# Logic_-_Copy.net
KiCad netlist of a schematic drawn in EAGLE
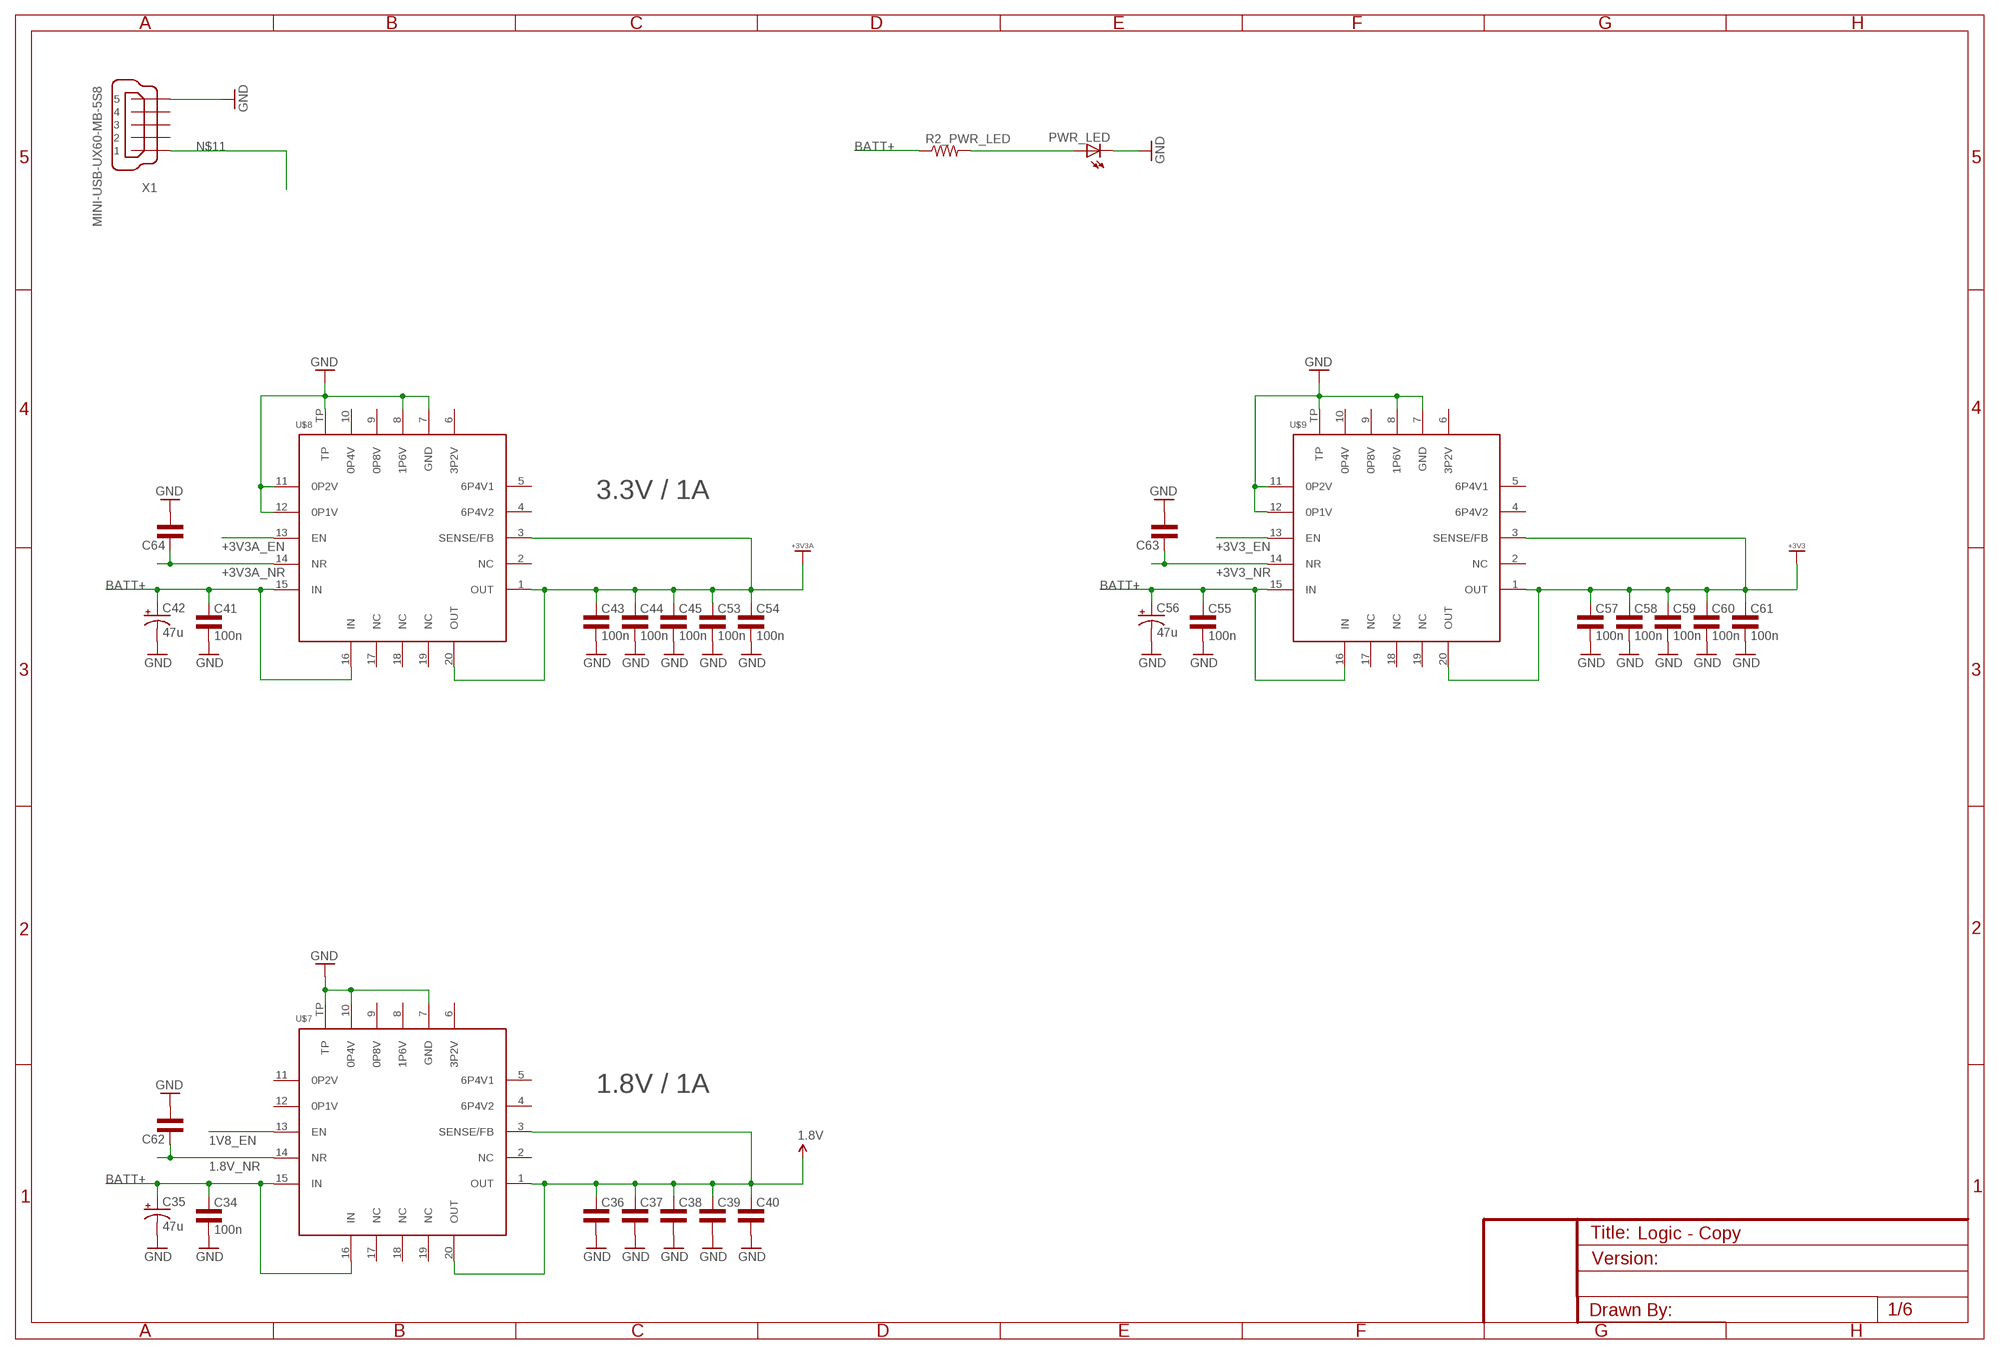
[diagram p0: schematic, sheet 1]
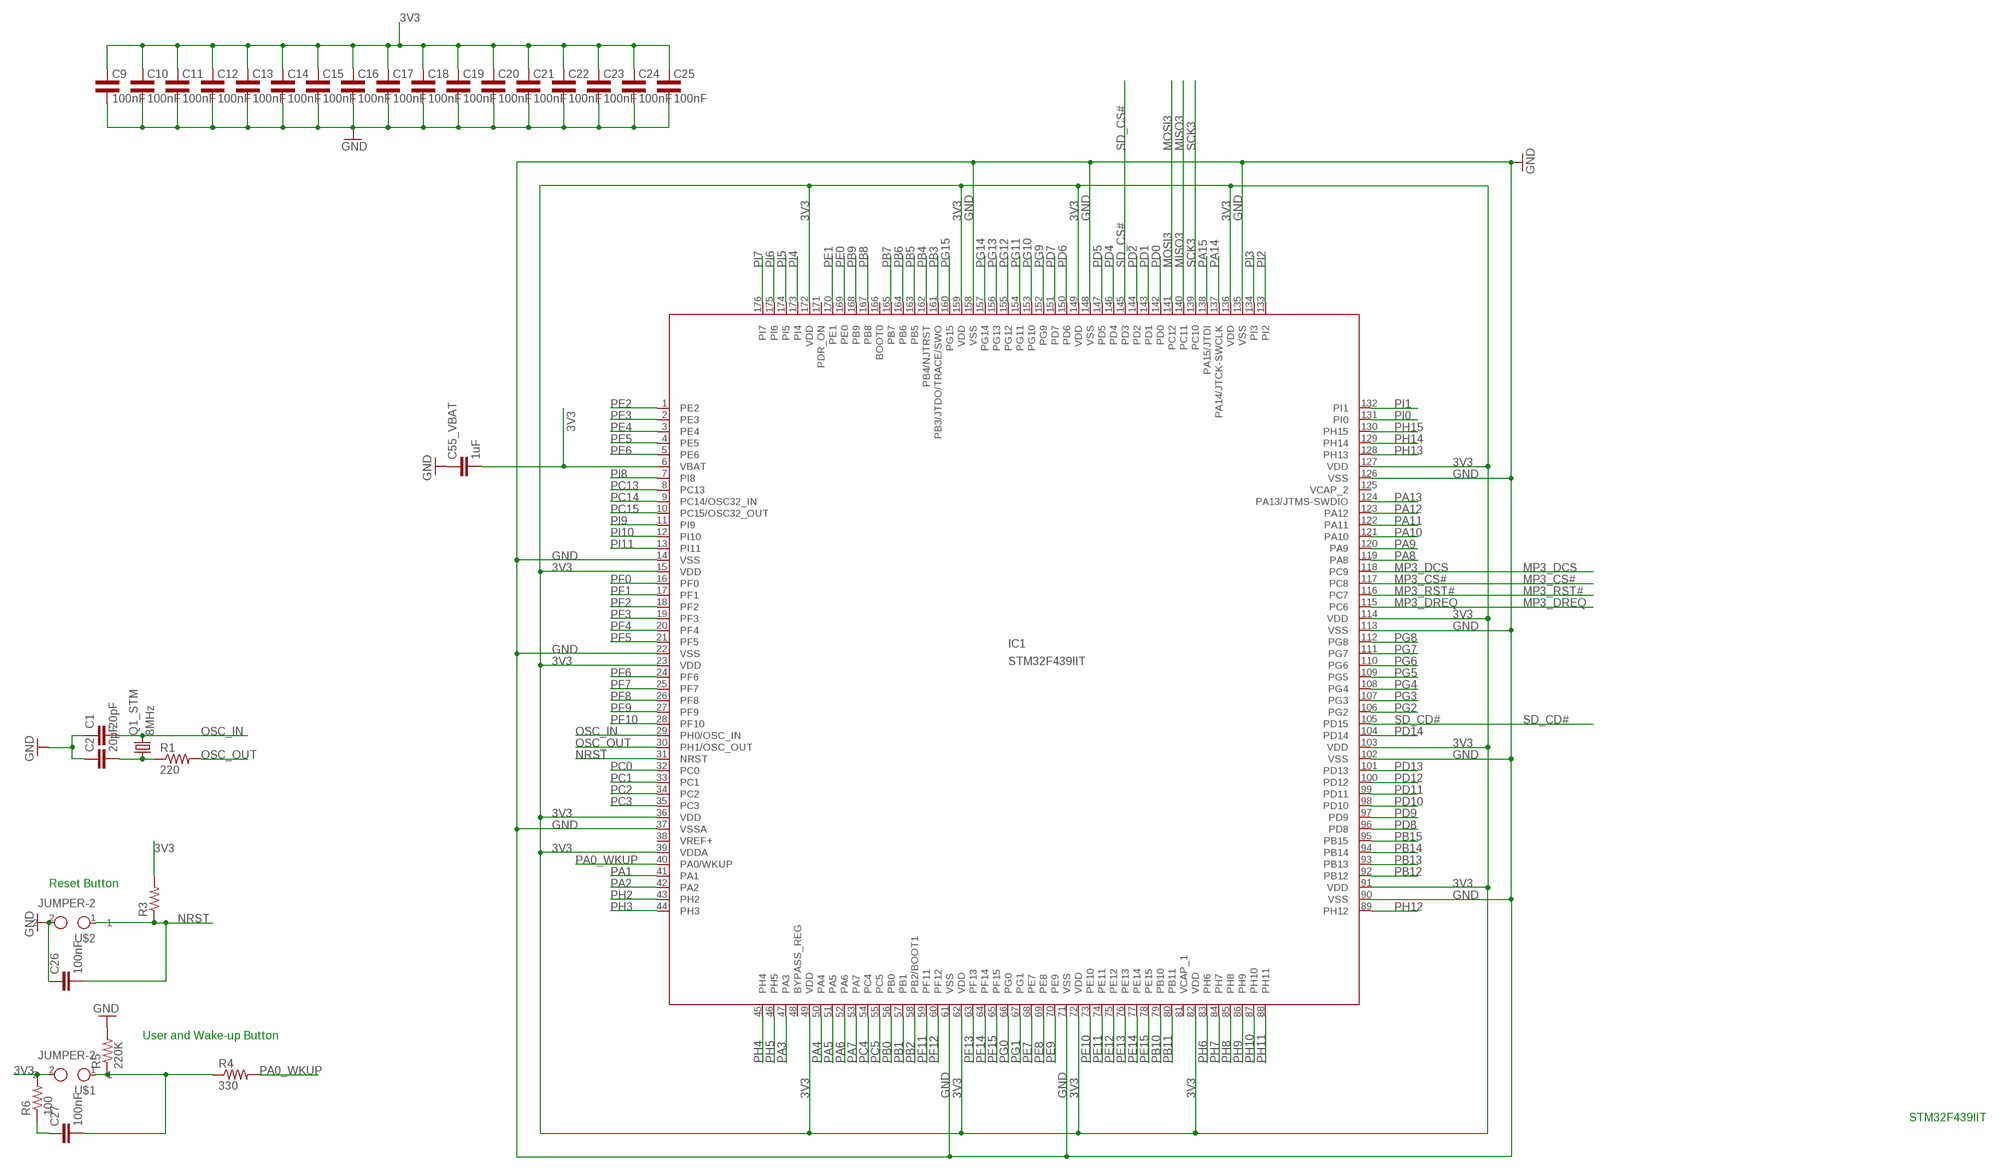
[diagram p1: schematic, sheet 2]
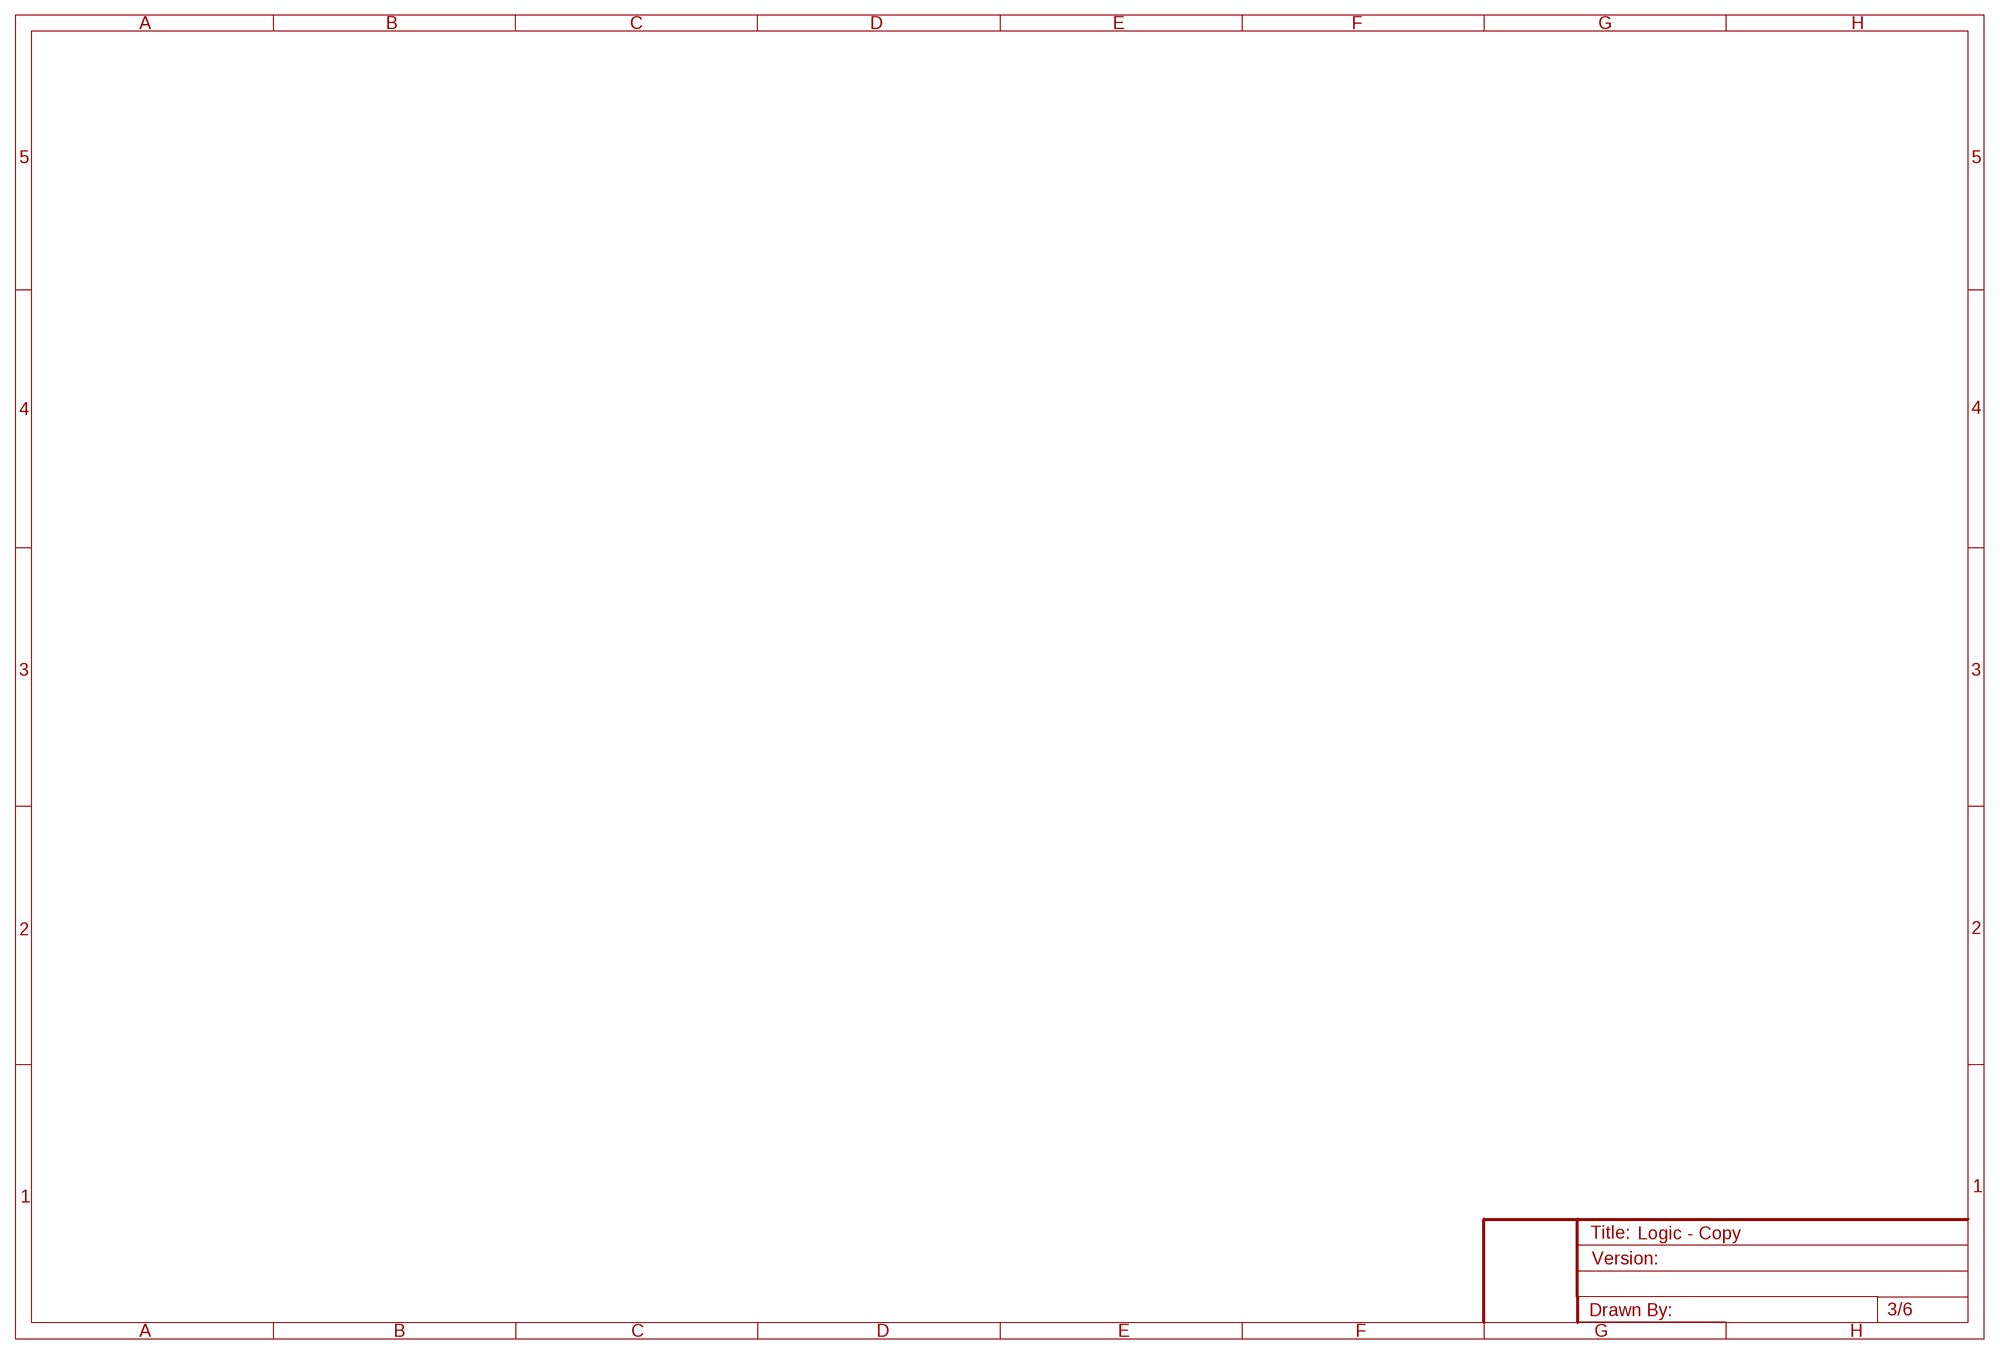
[diagram p2: schematic, sheet 3]
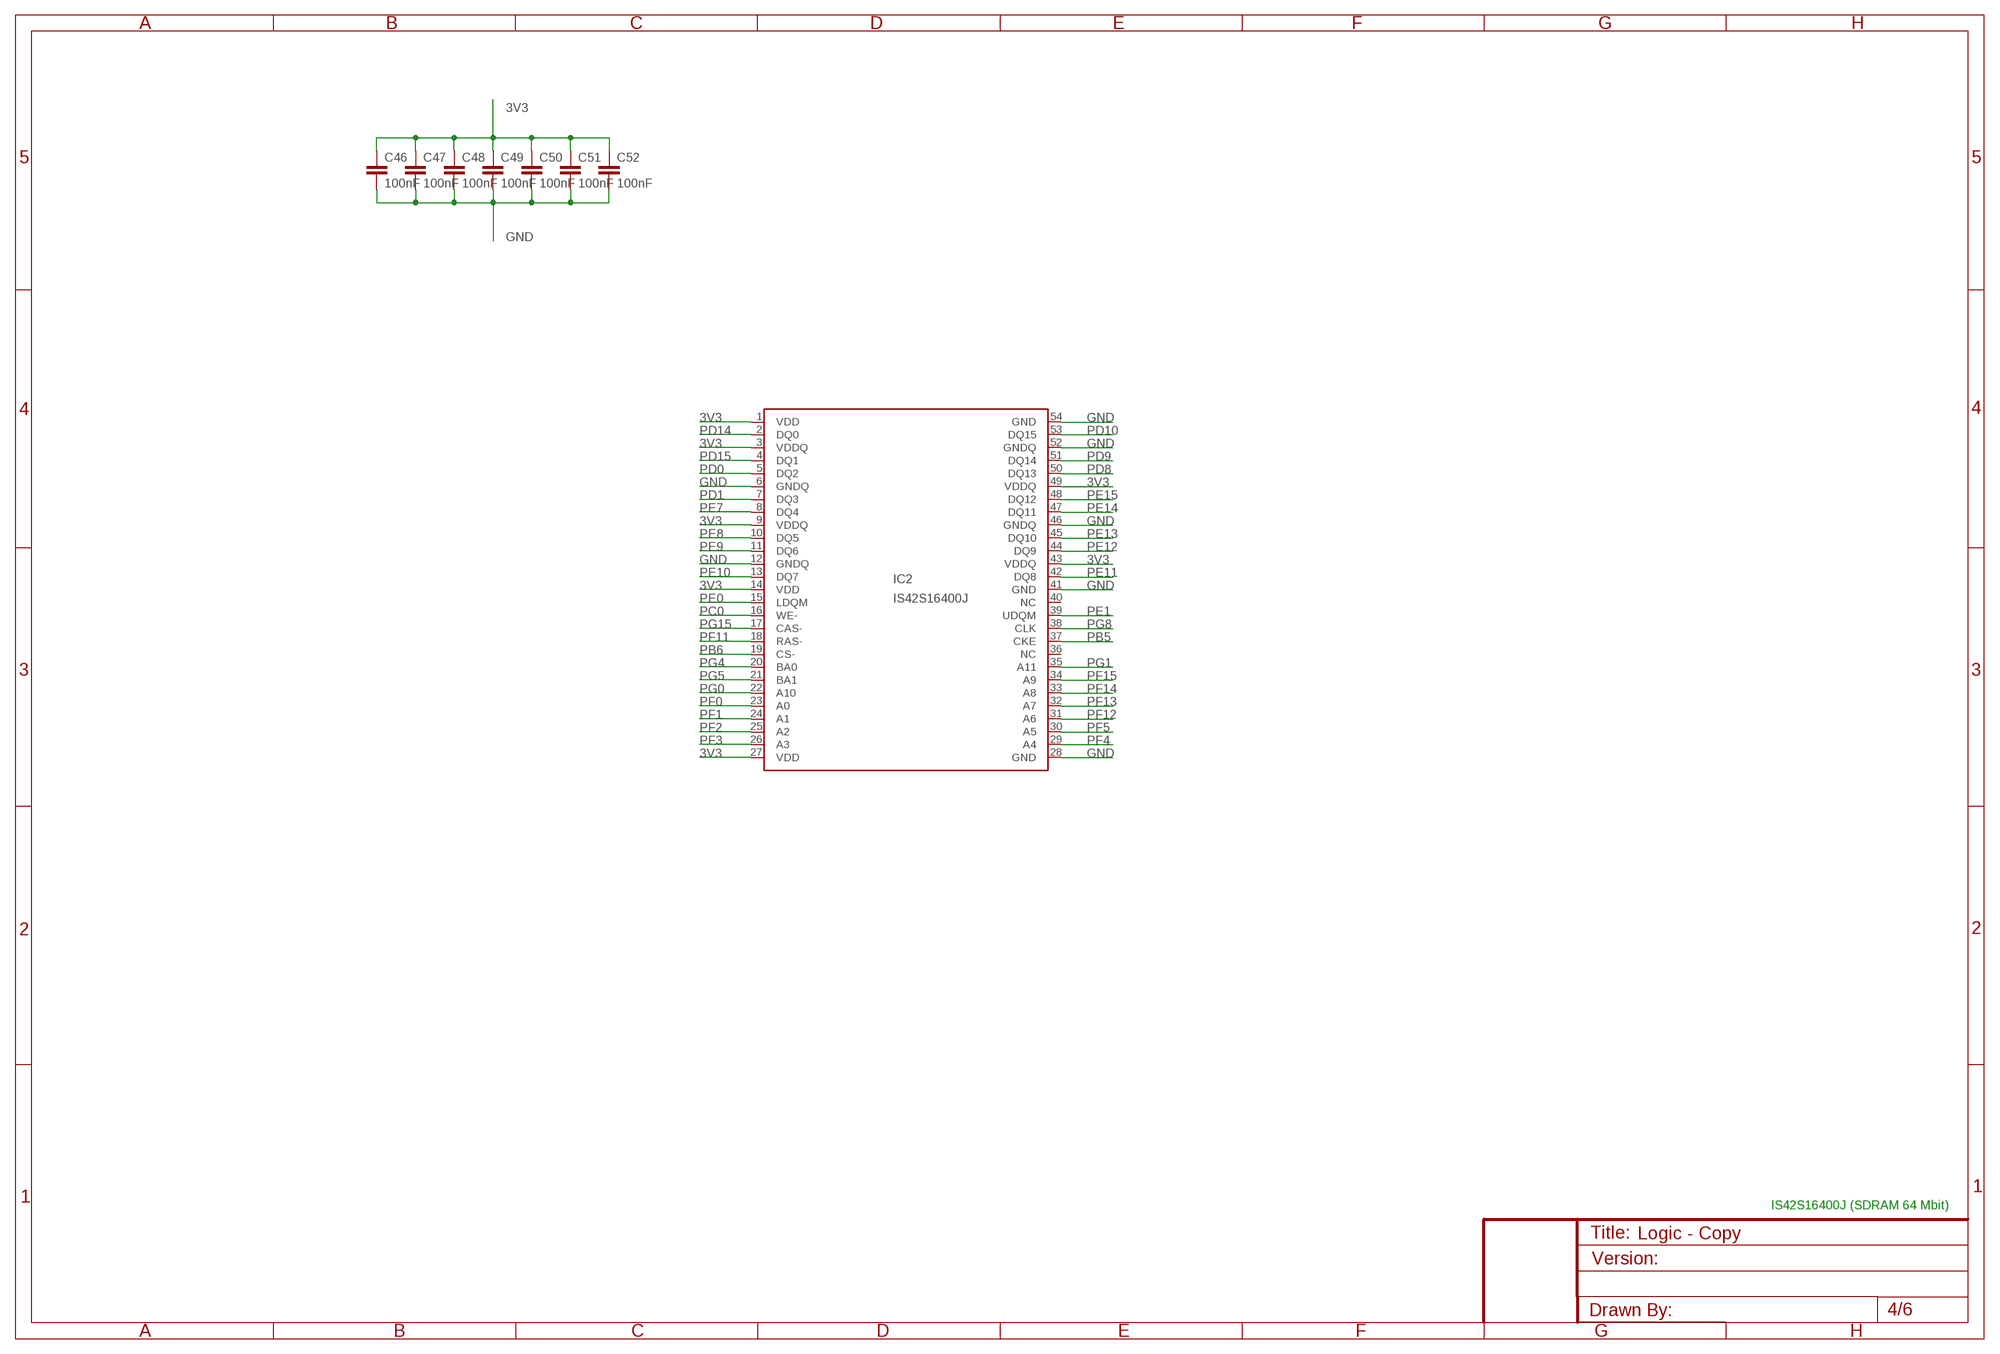
[diagram p3: schematic, sheet 4]
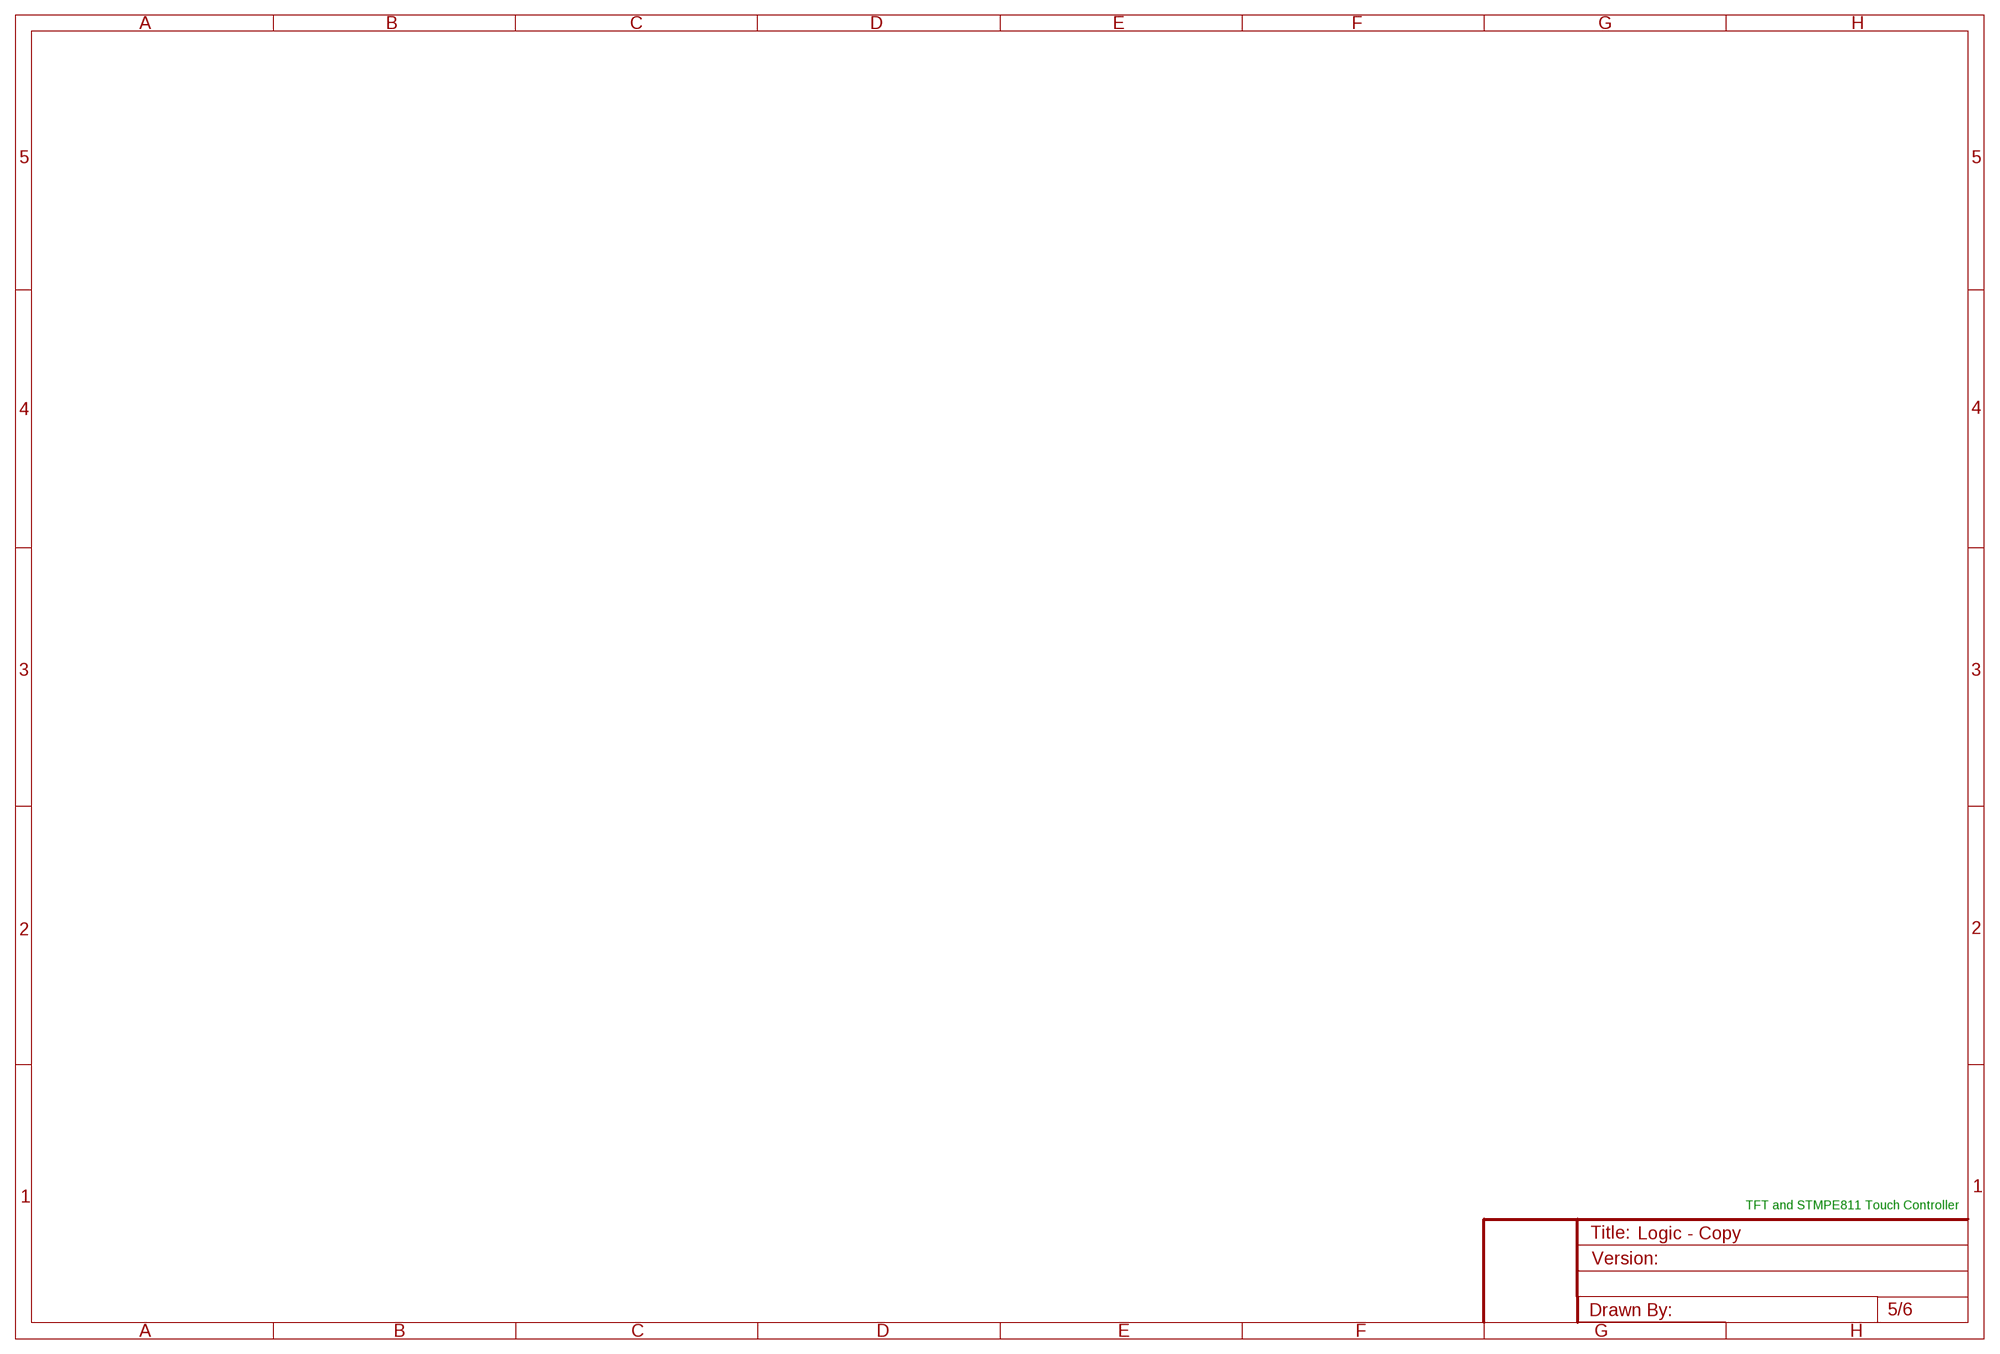
[diagram p4: schematic, sheet 5]
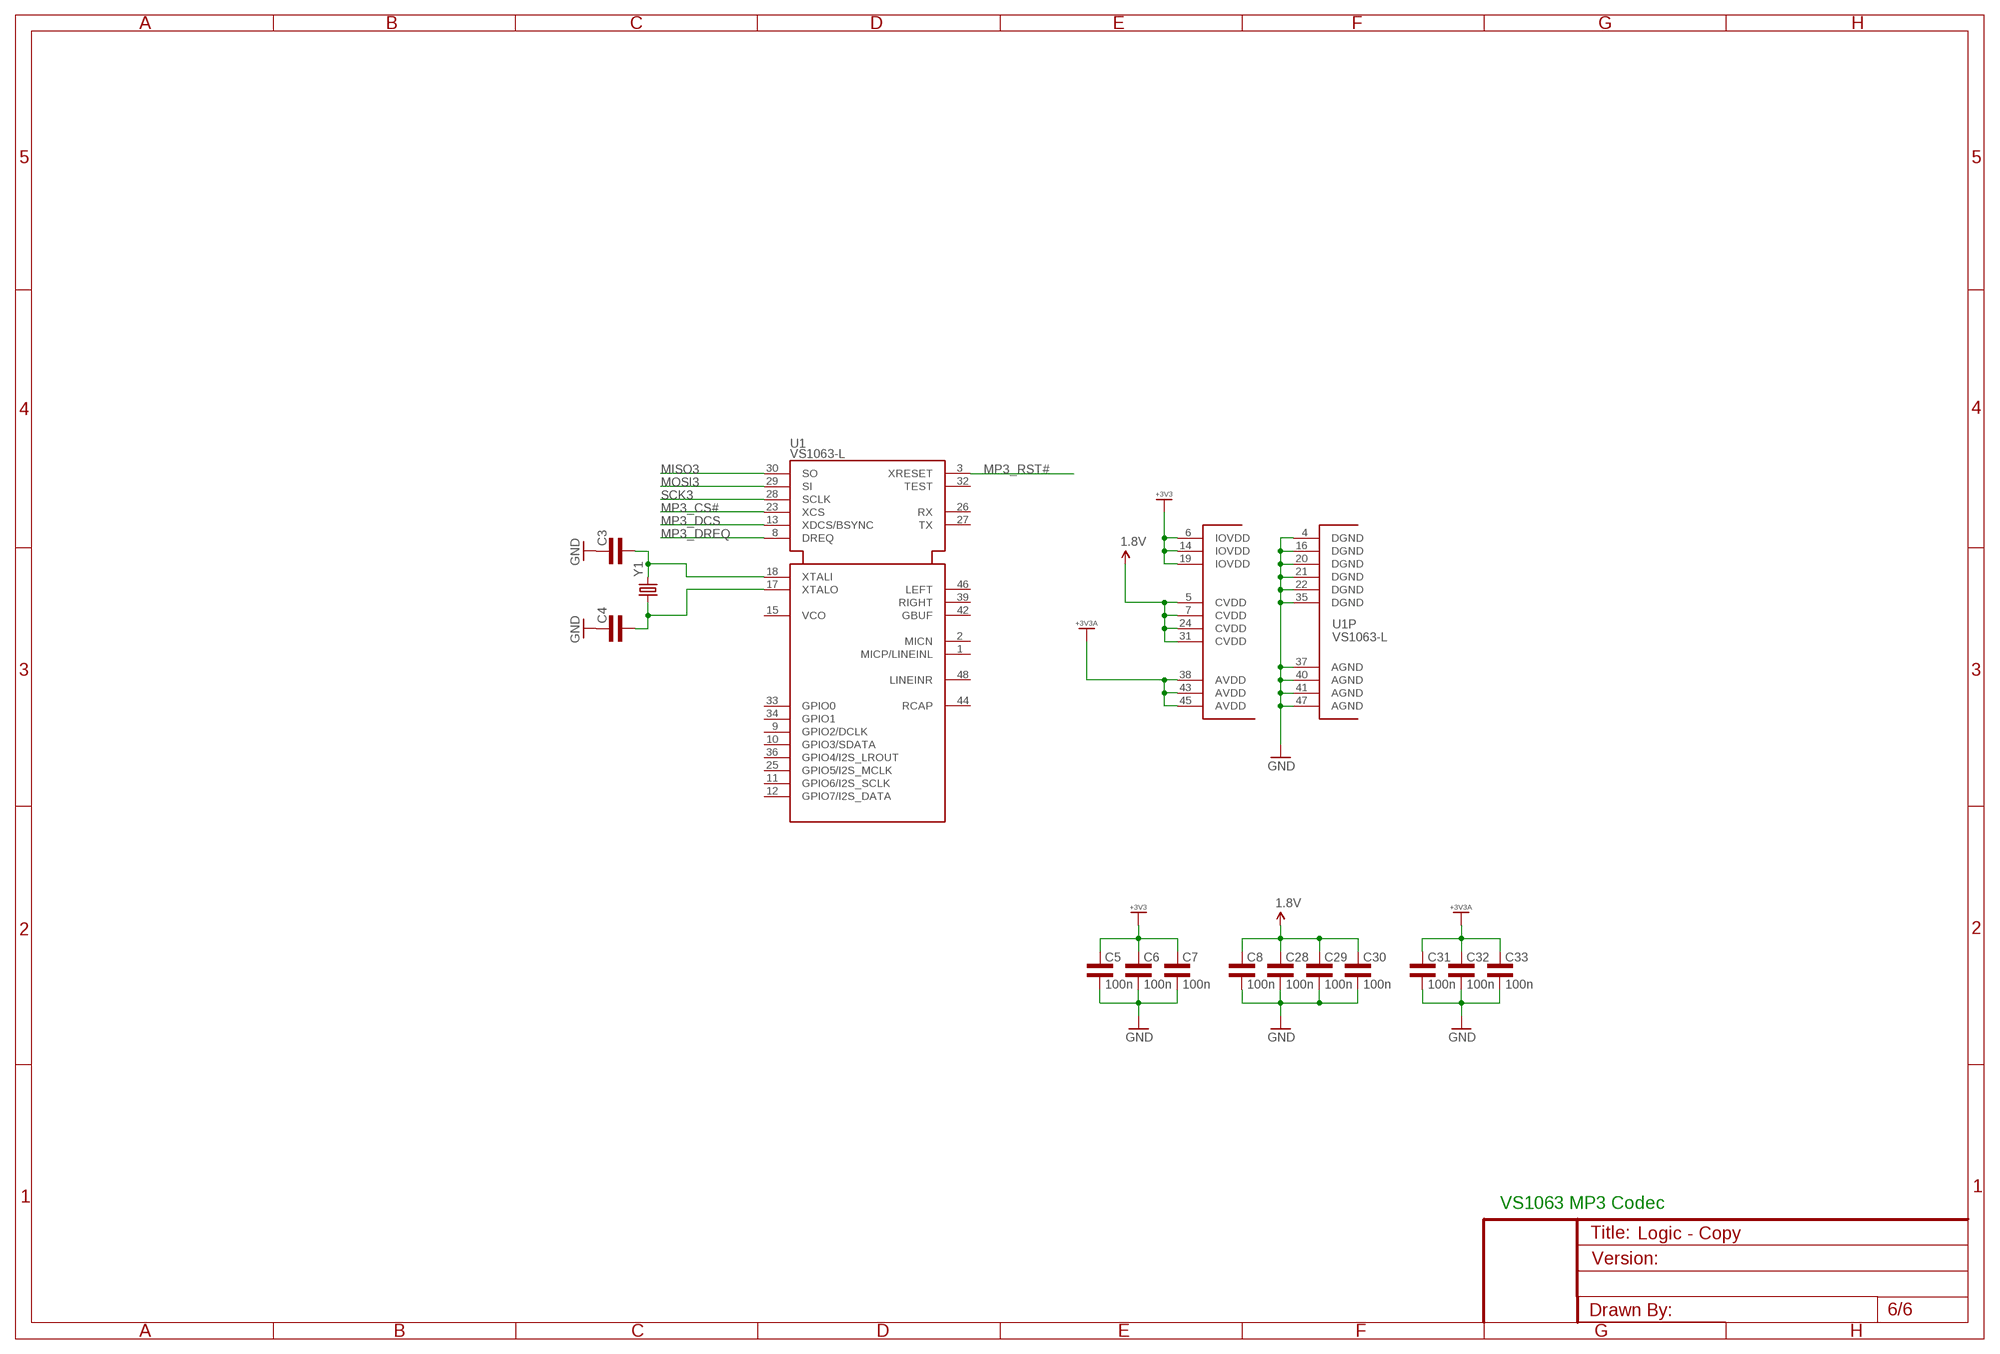
[diagram p5: schematic, sheet 6]

(export (version "E")
  (design (tool "Eeschema 10.0.6"))
  (components
    (comp (ref "C3")
      (value "CAP0603L3")
      (footprint "eagle-import:0603L3")
      (libsource (lib "eagle-import") (part "CAP0603L3"))
    )
    (comp (ref "C4")
      (value "CAP0603L3")
      (footprint "eagle-import:0603L3")
      (libsource (lib "eagle-import") (part "CAP0603L3"))
    )
    (comp (ref "C5")
      (value "100n")
      (footprint "eagle-import:0402L3")
      (libsource (lib "eagle-import") (part "CAP0402L3"))
    )
    (comp (ref "C6")
      (value "100n")
      (footprint "eagle-import:0402L3")
      (libsource (lib "eagle-import") (part "CAP0402L3"))
    )
    (comp (ref "C7")
      (value "100n")
      (footprint "eagle-import:0402L3")
      (libsource (lib "eagle-import") (part "CAP0402L3"))
    )
    (comp (ref "C8")
      (value "100n")
      (footprint "eagle-import:0402L3")
      (libsource (lib "eagle-import") (part "CAP0402L3"))
    )
    (comp (ref "C28")
      (value "100n")
      (footprint "eagle-import:0402L3")
      (libsource (lib "eagle-import") (part "CAP0402L3"))
    )
    (comp (ref "C29")
      (value "100n")
      (footprint "eagle-import:0402L3")
      (libsource (lib "eagle-import") (part "CAP0402L3"))
    )
    (comp (ref "C30")
      (value "100n")
      (footprint "eagle-import:0402L3")
      (libsource (lib "eagle-import") (part "CAP0402L3"))
    )
    (comp (ref "C31")
      (value "100n")
      (footprint "eagle-import:0402L3")
      (libsource (lib "eagle-import") (part "CAP0402L3"))
    )
    (comp (ref "C32")
      (value "100n")
      (footprint "eagle-import:0402L3")
      (libsource (lib "eagle-import") (part "CAP0402L3"))
    )
    (comp (ref "C33")
      (value "100n")
      (footprint "eagle-import:0402L3")
      (libsource (lib "eagle-import") (part "CAP0402L3"))
    )
    (comp (ref "U1")
      (value "VS1063-L")
      (footprint "eagle-import:LQFP48")
      (libsource (lib "eagle-import") (part "VS1063-L"))
    )
    (comp (ref "Y1")
      (value "CRYSTALHC49US")
      (footprint "eagle-import:HC49US")
      (libsource (lib "eagle-import") (part "CRYSTALHC49US"))
    )
    (comp (ref "C1")
      (value "20pF")
      (footprint "eagle-import:C0402")
      (libsource (lib "eagle-import") (part "resistor_C-EUC0402"))
    )
    (comp (ref "C2")
      (value "20pF")
      (footprint "eagle-import:C0402")
      (libsource (lib "eagle-import") (part "resistor_C-EUC0402"))
    )
    (comp (ref "C9")
      (value "100nF")
      (footprint "eagle-import:0402L3")
      (libsource (lib "eagle-import") (part "CAP0402L3"))
    )
    (comp (ref "C10")
      (value "100nF")
      (footprint "eagle-import:0402L3")
      (libsource (lib "eagle-import") (part "CAP0402L3"))
    )
    (comp (ref "C11")
      (value "100nF")
      (footprint "eagle-import:0402L3")
      (libsource (lib "eagle-import") (part "CAP0402L3"))
    )
    (comp (ref "C12")
      (value "100nF")
      (footprint "eagle-import:0402L3")
      (libsource (lib "eagle-import") (part "CAP0402L3"))
    )
    (comp (ref "C13")
      (value "100nF")
      (footprint "eagle-import:0402L3")
      (libsource (lib "eagle-import") (part "CAP0402L3"))
    )
    (comp (ref "C14")
      (value "100nF")
      (footprint "eagle-import:0402L3")
      (libsource (lib "eagle-import") (part "CAP0402L3"))
    )
    (comp (ref "C15")
      (value "100nF")
      (footprint "eagle-import:0402L3")
      (libsource (lib "eagle-import") (part "CAP0402L3"))
    )
    (comp (ref "C16")
      (value "100nF")
      (footprint "eagle-import:0402L3")
      (libsource (lib "eagle-import") (part "CAP0402L3"))
    )
    (comp (ref "C17")
      (value "100nF")
      (footprint "eagle-import:0402L3")
      (libsource (lib "eagle-import") (part "CAP0402L3"))
    )
    (comp (ref "C18")
      (value "100nF")
      (footprint "eagle-import:0402L3")
      (libsource (lib "eagle-import") (part "CAP0402L3"))
    )
    (comp (ref "C19")
      (value "100nF")
      (footprint "eagle-import:0402L3")
      (libsource (lib "eagle-import") (part "CAP0402L3"))
    )
    (comp (ref "C20")
      (value "100nF")
      (footprint "eagle-import:0402L3")
      (libsource (lib "eagle-import") (part "CAP0402L3"))
    )
    (comp (ref "C21")
      (value "100nF")
      (footprint "eagle-import:0402L3")
      (libsource (lib "eagle-import") (part "CAP0402L3"))
    )
    (comp (ref "C22")
      (value "100nF")
      (footprint "eagle-import:0402L3")
      (libsource (lib "eagle-import") (part "CAP0402L3"))
    )
    (comp (ref "C23")
      (value "100nF")
      (footprint "eagle-import:0402L3")
      (libsource (lib "eagle-import") (part "CAP0402L3"))
    )
    (comp (ref "C24")
      (value "100nF")
      (footprint "eagle-import:0402L3")
      (libsource (lib "eagle-import") (part "CAP0402L3"))
    )
    (comp (ref "C25")
      (value "100nF")
      (footprint "eagle-import:0402L3")
      (libsource (lib "eagle-import") (part "CAP0402L3"))
    )
    (comp (ref "C26")
      (value "100nF")
      (footprint "eagle-import:C0402")
      (libsource (lib "eagle-import") (part "C-EUC0402"))
    )
    (comp (ref "C27")
      (value "100nF")
      (footprint "eagle-import:C0402")
      (libsource (lib "eagle-import") (part "C-EUC0402"))
    )
    (comp (ref "C55_VBAT")
      (value "1uF")
      (footprint "eagle-import:C0402")
      (libsource (lib "eagle-import") (part "C-EUC0402"))
    )
    (comp (ref "IC1")
      (value "STM32F439IIT")
      (footprint "eagle-import:LQFP-176")
      (libsource (lib "eagle-import") (part "STM32F439IIT"))
    )
    (comp (ref "Q1_STM")
      (value "8MHz")
      (footprint "eagle-import:CTS406")
      (libsource (lib "eagle-import") (part "CRYSTALCTS406"))
    )
    (comp (ref "R1")
      (value "220")
      (footprint "eagle-import:0402-RES")
      (libsource (lib "eagle-import") (part "RESISTOR0402-RES"))
    )
    (comp (ref "R3")
      (value "RESISTOR0402-RES")
      (footprint "eagle-import:0402-RES")
      (libsource (lib "eagle-import") (part "RESISTOR0402-RES"))
    )
    (comp (ref "R4")
      (value "330")
      (footprint "eagle-import:0402-RES")
      (libsource (lib "eagle-import") (part "RESISTOR0402-RES"))
    )
    (comp (ref "R5")
      (value "220K")
      (footprint "eagle-import:0402-RES")
      (libsource (lib "eagle-import") (part "RESISTOR0402-RES"))
    )
    (comp (ref "R6")
      (value "100")
      (footprint "eagle-import:0402-RES")
      (libsource (lib "eagle-import") (part "RESISTOR0402-RES"))
    )
    (comp (ref "U$1")
      (value "JUMPER-2")
      (footprint "eagle-import:1X02")
      (libsource (lib "eagle-import") (part "JUMPER-2"))
    )
    (comp (ref "U$2")
      (value "JUMPER-2")
      (footprint "eagle-import:1X02")
      (libsource (lib "eagle-import") (part "JUMPER-2"))
    )
    (comp (ref "C34")
      (value "100n")
      (footprint "eagle-import:0805L3")
      (libsource (lib "eagle-import") (part "CAP0805L3"))
    )
    (comp (ref "C35")
      (value "47u")
      (footprint "eagle-import:CT3528")
      (libsource (lib "eagle-import") (part "CPOL-USCT3528"))
    )
    (comp (ref "C36")
      (value "CAP0805L3")
      (footprint "eagle-import:0805L3")
      (libsource (lib "eagle-import") (part "CAP0805L3"))
    )
    (comp (ref "C37")
      (value "CAP0805L3")
      (footprint "eagle-import:0805L3")
      (libsource (lib "eagle-import") (part "CAP0805L3"))
    )
    (comp (ref "C38")
      (value "CAP0805L3")
      (footprint "eagle-import:0805L3")
      (libsource (lib "eagle-import") (part "CAP0805L3"))
    )
    (comp (ref "C39")
      (value "CAP0805L3")
      (footprint "eagle-import:0805L3")
      (libsource (lib "eagle-import") (part "CAP0805L3"))
    )
    (comp (ref "C40")
      (value "CAP0805L3")
      (footprint "eagle-import:0805L3")
      (libsource (lib "eagle-import") (part "CAP0805L3"))
    )
    (comp (ref "C41")
      (value "100n")
      (footprint "eagle-import:0805L3")
      (libsource (lib "eagle-import") (part "CAP0805L3"))
    )
    (comp (ref "C42")
      (value "47u")
      (footprint "eagle-import:CT3528")
      (libsource (lib "eagle-import") (part "CPOL-USCT3528"))
    )
    (comp (ref "C43")
      (value "100n")
      (footprint "eagle-import:0805L3")
      (libsource (lib "eagle-import") (part "CAP0805L3"))
    )
    (comp (ref "C44")
      (value "100n")
      (footprint "eagle-import:0805L3")
      (libsource (lib "eagle-import") (part "CAP0805L3"))
    )
    (comp (ref "C45")
      (value "100n")
      (footprint "eagle-import:0805L3")
      (libsource (lib "eagle-import") (part "CAP0805L3"))
    )
    (comp (ref "C53")
      (value "100n")
      (footprint "eagle-import:0805L3")
      (libsource (lib "eagle-import") (part "CAP0805L3"))
    )
    (comp (ref "C54")
      (value "100n")
      (footprint "eagle-import:0805L3")
      (libsource (lib "eagle-import") (part "CAP0805L3"))
    )
    (comp (ref "C55")
      (value "100n")
      (footprint "eagle-import:0805L3")
      (libsource (lib "eagle-import") (part "CAP0805L3"))
    )
    (comp (ref "C56")
      (value "47u")
      (footprint "eagle-import:CT3528")
      (libsource (lib "eagle-import") (part "CPOL-USCT3528"))
    )
    (comp (ref "C57")
      (value "100n")
      (footprint "eagle-import:0805L3")
      (libsource (lib "eagle-import") (part "CAP0805L3"))
    )
    (comp (ref "C58")
      (value "100n")
      (footprint "eagle-import:0805L3")
      (libsource (lib "eagle-import") (part "CAP0805L3"))
    )
    (comp (ref "C59")
      (value "100n")
      (footprint "eagle-import:0805L3")
      (libsource (lib "eagle-import") (part "CAP0805L3"))
    )
    (comp (ref "C60")
      (value "100n")
      (footprint "eagle-import:0805L3")
      (libsource (lib "eagle-import") (part "CAP0805L3"))
    )
    (comp (ref "C61")
      (value "100n")
      (footprint "eagle-import:0805L3")
      (libsource (lib "eagle-import") (part "CAP0805L3"))
    )
    (comp (ref "C62")
      (value "CAP0402L3")
      (footprint "eagle-import:0402L3")
      (libsource (lib "eagle-import") (part "CAP0402L3"))
    )
    (comp (ref "C63")
      (value "CAP0402L3")
      (footprint "eagle-import:0402L3")
      (libsource (lib "eagle-import") (part "CAP0402L3"))
    )
    (comp (ref "C64")
      (value "CAP0402L3")
      (footprint "eagle-import:0402L3")
      (libsource (lib "eagle-import") (part "CAP0402L3"))
    )
    (comp (ref "PWR_LED")
      (value "LEDCHIP-LED0603")
      (footprint "eagle-import:CHIP-LED0603")
      (libsource (lib "eagle-import") (part "LEDCHIP-LED0603"))
    )
    (comp (ref "R2_PWR_LED")
      (value "RESISTOR0402-RES")
      (footprint "eagle-import:0402-RES")
      (libsource (lib "eagle-import") (part "RESISTOR0402-RES"))
    )
    (comp (ref "U$7")
      (value "POWER-SUPPLY_POS_V1_TI_LDO_TPS7A4700")
      (footprint "eagle-import:POWER-SUPPLY_POS_V1_TI_LDO_VQFN-20")
      (libsource (lib "eagle-import") (part "POWER-SUPPLY_POS_V1_TI_LDO_TPS7A4700"))
    )
    (comp (ref "U$8")
      (value "POWER-SUPPLY_POS_V1_TI_LDO_TPS7A4700")
      (footprint "eagle-import:POWER-SUPPLY_POS_V1_TI_LDO_VQFN-20")
      (libsource (lib "eagle-import") (part "POWER-SUPPLY_POS_V1_TI_LDO_TPS7A4700"))
    )
    (comp (ref "U$9")
      (value "POWER-SUPPLY_POS_V1_TI_LDO_TPS7A4700")
      (footprint "eagle-import:POWER-SUPPLY_POS_V1_TI_LDO_VQFN-20")
      (libsource (lib "eagle-import") (part "POWER-SUPPLY_POS_V1_TI_LDO_TPS7A4700"))
    )
    (comp (ref "X1")
      (value "MINI-USB-UX60-MB-5S8")
      (footprint "eagle-import:UX60-MB-5S8")
      (libsource (lib "eagle-import") (part "MINI-USB-UX60-MB-5S8"))
    )
    (comp (ref "C46")
      (value "100nF")
      (footprint "eagle-import:C0402")
      (libsource (lib "eagle-import") (part "C-EUC0402"))
    )
    (comp (ref "C47")
      (value "100nF")
      (footprint "eagle-import:C0402")
      (libsource (lib "eagle-import") (part "C-EUC0402"))
    )
    (comp (ref "C48")
      (value "100nF")
      (footprint "eagle-import:C0402")
      (libsource (lib "eagle-import") (part "C-EUC0402"))
    )
    (comp (ref "C49")
      (value "100nF")
      (footprint "eagle-import:C0402")
      (libsource (lib "eagle-import") (part "C-EUC0402"))
    )
    (comp (ref "C50")
      (value "100nF")
      (footprint "eagle-import:C0402")
      (libsource (lib "eagle-import") (part "C-EUC0402"))
    )
    (comp (ref "C51")
      (value "100nF")
      (footprint "eagle-import:C0402")
      (libsource (lib "eagle-import") (part "C-EUC0402"))
    )
    (comp (ref "C52")
      (value "100nF")
      (footprint "eagle-import:C0402")
      (libsource (lib "eagle-import") (part "C-EUC0402"))
    )
    (comp (ref "IC2")
      (value "IS42S16400J")
      (footprint "eagle-import:TSOP-2")
      (libsource (lib "eagle-import") (part "IS42S16400J"))
    )
  )
  (nets
    (net (code "1") (name "+3V3") (class "Default")
      (node (ref "C5") (pin "P$1") (pinfunction "1_P$1") (pintype "bidirectional"))
      (node (ref "C57") (pin "1") (pinfunction "1_1") (pintype "bidirectional"))
      (node (ref "C58") (pin "1") (pinfunction "1_1") (pintype "bidirectional"))
      (node (ref "C59") (pin "1") (pinfunction "1_1") (pintype "bidirectional"))
      (node (ref "C6") (pin "P$1") (pinfunction "1_P$1") (pintype "bidirectional"))
      (node (ref "C60") (pin "1") (pinfunction "1_1") (pintype "bidirectional"))
      (node (ref "C61") (pin "1") (pinfunction "1_1") (pintype "bidirectional"))
      (node (ref "C7") (pin "P$1") (pinfunction "1_P$1") (pintype "bidirectional"))
      (node (ref "U$9") (pin "1") (pinfunction "OUT_1") (pintype "bidirectional"))
      (node (ref "U$9") (pin "20") (pinfunction "OUT_20") (pintype "bidirectional"))
      (node (ref "U$9") (pin "3") (pinfunction "SENSE/FB_3") (pintype "bidirectional"))
      (node (ref "U1") (pin "14") (pinfunction "IOVDD_14") (pintype "power_in"))
      (node (ref "U1") (pin "19") (pinfunction "IOVDD_19") (pintype "power_in"))
      (node (ref "U1") (pin "6") (pinfunction "IOVDD_6") (pintype "power_in"))
    )
    (net (code "2") (name "+3V3A") (class "Default")
      (node (ref "C31") (pin "P$1") (pinfunction "1_P$1") (pintype "bidirectional"))
      (node (ref "C32") (pin "P$1") (pinfunction "1_P$1") (pintype "bidirectional"))
      (node (ref "C33") (pin "P$1") (pinfunction "1_P$1") (pintype "bidirectional"))
      (node (ref "C43") (pin "1") (pinfunction "1_1") (pintype "bidirectional"))
      (node (ref "C44") (pin "1") (pinfunction "1_1") (pintype "bidirectional"))
      (node (ref "C45") (pin "1") (pinfunction "1_1") (pintype "bidirectional"))
      (node (ref "C53") (pin "1") (pinfunction "1_1") (pintype "bidirectional"))
      (node (ref "C54") (pin "1") (pinfunction "1_1") (pintype "bidirectional"))
      (node (ref "U$8") (pin "1") (pinfunction "OUT_1") (pintype "bidirectional"))
      (node (ref "U$8") (pin "20") (pinfunction "OUT_20") (pintype "bidirectional"))
      (node (ref "U$8") (pin "3") (pinfunction "SENSE/FB_3") (pintype "bidirectional"))
      (node (ref "U1") (pin "38") (pinfunction "AVDD_38") (pintype "power_in"))
      (node (ref "U1") (pin "43") (pinfunction "AVDD_43") (pintype "power_in"))
      (node (ref "U1") (pin "45") (pinfunction "AVDD_45") (pintype "power_in"))
    )
    (net (code "3") (name "+3V3A_EN") (class "Default")
      (node (ref "U$8") (pin "13") (pinfunction "EN_13") (pintype "bidirectional"))
    )
    (net (code "4") (name "+3V3A_NR") (class "Default")
      (node (ref "C64") (pin "P$1") (pinfunction "1_P$1") (pintype "bidirectional"))
      (node (ref "U$8") (pin "14") (pinfunction "NR_14") (pintype "bidirectional"))
    )
    (net (code "5") (name "+3V3_EN") (class "Default")
      (node (ref "U$9") (pin "13") (pinfunction "EN_13") (pintype "bidirectional"))
    )
    (net (code "6") (name "+3V3_NR") (class "Default")
      (node (ref "C63") (pin "P$1") (pinfunction "1_P$1") (pintype "bidirectional"))
      (node (ref "U$9") (pin "14") (pinfunction "NR_14") (pintype "bidirectional"))
    )
    (net (code "7") (name "1.8V") (class "Default")
      (node (ref "C28") (pin "P$1") (pinfunction "1_P$1") (pintype "bidirectional"))
      (node (ref "C29") (pin "P$1") (pinfunction "1_P$1") (pintype "bidirectional"))
      (node (ref "C30") (pin "P$1") (pinfunction "1_P$1") (pintype "bidirectional"))
      (node (ref "C36") (pin "1") (pinfunction "1_1") (pintype "bidirectional"))
      (node (ref "C37") (pin "1") (pinfunction "1_1") (pintype "bidirectional"))
      (node (ref "C38") (pin "1") (pinfunction "1_1") (pintype "bidirectional"))
      (node (ref "C39") (pin "1") (pinfunction "1_1") (pintype "bidirectional"))
      (node (ref "C40") (pin "1") (pinfunction "1_1") (pintype "bidirectional"))
      (node (ref "C8") (pin "P$1") (pinfunction "1_P$1") (pintype "bidirectional"))
      (node (ref "U$7") (pin "1") (pinfunction "OUT_1") (pintype "bidirectional"))
      (node (ref "U$7") (pin "20") (pinfunction "OUT_20") (pintype "bidirectional"))
      (node (ref "U$7") (pin "3") (pinfunction "SENSE/FB_3") (pintype "bidirectional"))
      (node (ref "U1") (pin "24") (pinfunction "CVDD_24") (pintype "power_in"))
      (node (ref "U1") (pin "31") (pinfunction "CVDD_31") (pintype "power_in"))
      (node (ref "U1") (pin "5") (pinfunction "CVDD_5") (pintype "power_in"))
      (node (ref "U1") (pin "7") (pinfunction "CVDD_7") (pintype "power_in"))
    )
    (net (code "8") (name "1.8V_NR") (class "Default")
      (node (ref "C62") (pin "P$1") (pinfunction "1_P$1") (pintype "bidirectional"))
      (node (ref "U$7") (pin "14") (pinfunction "NR_14") (pintype "bidirectional"))
    )
    (net (code "9") (name "1V8_EN") (class "Default")
      (node (ref "U$7") (pin "13") (pinfunction "EN_13") (pintype "bidirectional"))
    )
    (net (code "10") (name "3V3") (class "Default")
      (node (ref "C10") (pin "P$1") (pinfunction "1_P$1") (pintype "bidirectional"))
      (node (ref "C11") (pin "P$1") (pinfunction "1_P$1") (pintype "bidirectional"))
      (node (ref "C12") (pin "P$1") (pinfunction "1_P$1") (pintype "bidirectional"))
      (node (ref "C13") (pin "P$1") (pinfunction "1_P$1") (pintype "bidirectional"))
      (node (ref "C14") (pin "P$1") (pinfunction "1_P$1") (pintype "bidirectional"))
      (node (ref "C15") (pin "P$1") (pinfunction "1_P$1") (pintype "bidirectional"))
      (node (ref "C16") (pin "P$1") (pinfunction "1_P$1") (pintype "bidirectional"))
      (node (ref "C17") (pin "P$1") (pinfunction "1_P$1") (pintype "bidirectional"))
      (node (ref "C18") (pin "P$1") (pinfunction "1_P$1") (pintype "bidirectional"))
      (node (ref "C19") (pin "P$1") (pinfunction "1_P$1") (pintype "bidirectional"))
      (node (ref "C20") (pin "P$1") (pinfunction "1_P$1") (pintype "bidirectional"))
      (node (ref "C21") (pin "P$1") (pinfunction "1_P$1") (pintype "bidirectional"))
      (node (ref "C22") (pin "P$1") (pinfunction "1_P$1") (pintype "bidirectional"))
      (node (ref "C23") (pin "P$1") (pinfunction "1_P$1") (pintype "bidirectional"))
      (node (ref "C24") (pin "P$1") (pinfunction "1_P$1") (pintype "bidirectional"))
      (node (ref "C25") (pin "P$1") (pinfunction "1_P$1") (pintype "bidirectional"))
      (node (ref "C46") (pin "1") (pinfunction "1_1") (pintype "passive"))
      (node (ref "C47") (pin "1") (pinfunction "1_1") (pintype "passive"))
      (node (ref "C48") (pin "1") (pinfunction "1_1") (pintype "passive"))
      (node (ref "C49") (pin "1") (pinfunction "1_1") (pintype "passive"))
      (node (ref "C50") (pin "1") (pinfunction "1_1") (pintype "passive"))
      (node (ref "C51") (pin "1") (pinfunction "1_1") (pintype "passive"))
      (node (ref "C52") (pin "1") (pinfunction "1_1") (pintype "passive"))
      (node (ref "C55_VBAT") (pin "2") (pinfunction "2_2") (pintype "passive"))
      (node (ref "C9") (pin "P$1") (pinfunction "1_P$1") (pintype "bidirectional"))
      (node (ref "IC1") (pin "103") (pinfunction "VDD_103") (pintype "power_in"))
      (node (ref "IC1") (pin "114") (pinfunction "VDD_114") (pintype "power_in"))
      (node (ref "IC1") (pin "127") (pinfunction "VDD_127") (pintype "power_in"))
      (node (ref "IC1") (pin "136") (pinfunction "VDD_136") (pintype "power_in"))
      (node (ref "IC1") (pin "149") (pinfunction "VDD_149") (pintype "power_in"))
      (node (ref "IC1") (pin "15") (pinfunction "VDD_15") (pintype "power_in"))
      (node (ref "IC1") (pin "159") (pinfunction "VDD_159") (pintype "power_in"))
      (node (ref "IC1") (pin "172") (pinfunction "VDD_172") (pintype "power_in"))
      (node (ref "IC1") (pin "23") (pinfunction "VDD_23") (pintype "power_in"))
      (node (ref "IC1") (pin "36") (pinfunction "VDD_36") (pintype "power_in"))
      (node (ref "IC1") (pin "39") (pinfunction "VDDA_39") (pintype "power_in"))
      (node (ref "IC1") (pin "49") (pinfunction "VDD_49") (pintype "power_in"))
      (node (ref "IC1") (pin "6") (pinfunction "VBAT_6") (pintype "power_in"))
      (node (ref "IC1") (pin "62") (pinfunction "VDD_62") (pintype "bidirectional"))
      (node (ref "IC1") (pin "72") (pinfunction "VDD_72") (pintype "power_in"))
      (node (ref "IC1") (pin "82") (pinfunction "VDD_82") (pintype "power_in"))
      (node (ref "IC1") (pin "91") (pinfunction "VDD_91") (pintype "power_in"))
      (node (ref "IC2") (pin "1") (pinfunction "VDD_1") (pintype "power_in"))
      (node (ref "IC2") (pin "14") (pinfunction "VDD_14") (pintype "power_in"))
      (node (ref "IC2") (pin "27") (pinfunction "VDD_27") (pintype "power_in"))
      (node (ref "IC2") (pin "3") (pinfunction "VDDQ_3") (pintype "power_in"))
      (node (ref "IC2") (pin "43") (pinfunction "VDDQ_43") (pintype "power_in"))
      (node (ref "IC2") (pin "49") (pinfunction "VDDQ_49") (pintype "power_in"))
      (node (ref "IC2") (pin "9") (pinfunction "VDDQ_9") (pintype "power_in"))
      (node (ref "R3") (pin "2") (pinfunction "2_2") (pintype "passive"))
      (node (ref "R6") (pin "2") (pinfunction "2_2") (pintype "passive"))
      (node (ref "U$1") (pin "2") (pinfunction "2_2") (pintype "bidirectional"))
    )
    (net (code "11") (name "BATT+") (class "Default")
      (node (ref "C34") (pin "1") (pinfunction "1_1") (pintype "bidirectional"))
      (node (ref "C35") (pin "+") (pinfunction "+_+") (pintype "passive"))
      (node (ref "C41") (pin "1") (pinfunction "1_1") (pintype "bidirectional"))
      (node (ref "C42") (pin "+") (pinfunction "+_+") (pintype "passive"))
      (node (ref "C55") (pin "1") (pinfunction "1_1") (pintype "bidirectional"))
      (node (ref "C56") (pin "+") (pinfunction "+_+") (pintype "passive"))
      (node (ref "R2_PWR_LED") (pin "1") (pinfunction "1_1") (pintype "passive"))
      (node (ref "U$7") (pin "15") (pinfunction "IN_15") (pintype "bidirectional"))
      (node (ref "U$7") (pin "16") (pinfunction "IN_16") (pintype "bidirectional"))
      (node (ref "U$8") (pin "15") (pinfunction "IN_15") (pintype "bidirectional"))
      (node (ref "U$8") (pin "16") (pinfunction "IN_16") (pintype "bidirectional"))
      (node (ref "U$9") (pin "15") (pinfunction "IN_15") (pintype "bidirectional"))
      (node (ref "U$9") (pin "16") (pinfunction "IN_16") (pintype "bidirectional"))
    )
    (net (code "12") (name "GND") (class "Default")
      (node (ref "C1") (pin "1") (pinfunction "1_1") (pintype "passive"))
      (node (ref "C10") (pin "P$2") (pinfunction "2_P$2") (pintype "bidirectional"))
      (node (ref "C11") (pin "P$2") (pinfunction "2_P$2") (pintype "bidirectional"))
      (node (ref "C12") (pin "P$2") (pinfunction "2_P$2") (pintype "bidirectional"))
      (node (ref "C13") (pin "P$2") (pinfunction "2_P$2") (pintype "bidirectional"))
      (node (ref "C14") (pin "P$2") (pinfunction "2_P$2") (pintype "bidirectional"))
      (node (ref "C15") (pin "P$2") (pinfunction "2_P$2") (pintype "bidirectional"))
      (node (ref "C16") (pin "P$2") (pinfunction "2_P$2") (pintype "bidirectional"))
      (node (ref "C17") (pin "P$2") (pinfunction "2_P$2") (pintype "bidirectional"))
      (node (ref "C18") (pin "P$2") (pinfunction "2_P$2") (pintype "bidirectional"))
      (node (ref "C19") (pin "P$2") (pinfunction "2_P$2") (pintype "bidirectional"))
      (node (ref "C2") (pin "1") (pinfunction "1_1") (pintype "passive"))
      (node (ref "C20") (pin "P$2") (pinfunction "2_P$2") (pintype "bidirectional"))
      (node (ref "C21") (pin "P$2") (pinfunction "2_P$2") (pintype "bidirectional"))
      (node (ref "C22") (pin "P$2") (pinfunction "2_P$2") (pintype "bidirectional"))
      (node (ref "C23") (pin "P$2") (pinfunction "2_P$2") (pintype "bidirectional"))
      (node (ref "C24") (pin "P$2") (pinfunction "2_P$2") (pintype "bidirectional"))
      (node (ref "C25") (pin "P$2") (pinfunction "2_P$2") (pintype "bidirectional"))
      (node (ref "C26") (pin "1") (pinfunction "1_1") (pintype "passive"))
      (node (ref "C28") (pin "P$2") (pinfunction "2_P$2") (pintype "bidirectional"))
      (node (ref "C29") (pin "P$2") (pinfunction "2_P$2") (pintype "bidirectional"))
      (node (ref "C3") (pin "P$1") (pinfunction "1_P$1") (pintype "bidirectional"))
      (node (ref "C30") (pin "P$2") (pinfunction "2_P$2") (pintype "bidirectional"))
      (node (ref "C31") (pin "P$2") (pinfunction "2_P$2") (pintype "bidirectional"))
      (node (ref "C32") (pin "P$2") (pinfunction "2_P$2") (pintype "bidirectional"))
      (node (ref "C33") (pin "P$2") (pinfunction "2_P$2") (pintype "bidirectional"))
      (node (ref "C34") (pin "2") (pinfunction "2_2") (pintype "bidirectional"))
      (node (ref "C35") (pin "-") (pinfunction "-_-") (pintype "passive"))
      (node (ref "C36") (pin "2") (pinfunction "2_2") (pintype "bidirectional"))
      (node (ref "C37") (pin "2") (pinfunction "2_2") (pintype "bidirectional"))
      (node (ref "C38") (pin "2") (pinfunction "2_2") (pintype "bidirectional"))
      (node (ref "C39") (pin "2") (pinfunction "2_2") (pintype "bidirectional"))
      (node (ref "C4") (pin "P$1") (pinfunction "1_P$1") (pintype "bidirectional"))
      (node (ref "C40") (pin "2") (pinfunction "2_2") (pintype "bidirectional"))
      (node (ref "C41") (pin "2") (pinfunction "2_2") (pintype "bidirectional"))
      (node (ref "C42") (pin "-") (pinfunction "-_-") (pintype "passive"))
      (node (ref "C43") (pin "2") (pinfunction "2_2") (pintype "bidirectional"))
      (node (ref "C44") (pin "2") (pinfunction "2_2") (pintype "bidirectional"))
      (node (ref "C45") (pin "2") (pinfunction "2_2") (pintype "bidirectional"))
      (node (ref "C46") (pin "2") (pinfunction "2_2") (pintype "passive"))
      (node (ref "C47") (pin "2") (pinfunction "2_2") (pintype "passive"))
      (node (ref "C48") (pin "2") (pinfunction "2_2") (pintype "passive"))
      (node (ref "C49") (pin "2") (pinfunction "2_2") (pintype "passive"))
      (node (ref "C5") (pin "P$2") (pinfunction "2_P$2") (pintype "bidirectional"))
      (node (ref "C50") (pin "2") (pinfunction "2_2") (pintype "passive"))
      (node (ref "C51") (pin "2") (pinfunction "2_2") (pintype "passive"))
      (node (ref "C52") (pin "2") (pinfunction "2_2") (pintype "passive"))
      (node (ref "C53") (pin "2") (pinfunction "2_2") (pintype "bidirectional"))
      (node (ref "C54") (pin "2") (pinfunction "2_2") (pintype "bidirectional"))
      (node (ref "C55") (pin "2") (pinfunction "2_2") (pintype "bidirectional"))
      (node (ref "C55_VBAT") (pin "1") (pinfunction "1_1") (pintype "passive"))
      (node (ref "C56") (pin "-") (pinfunction "-_-") (pintype "passive"))
      (node (ref "C57") (pin "2") (pinfunction "2_2") (pintype "bidirectional"))
      (node (ref "C58") (pin "2") (pinfunction "2_2") (pintype "bidirectional"))
      (node (ref "C59") (pin "2") (pinfunction "2_2") (pintype "bidirectional"))
      (node (ref "C6") (pin "P$2") (pinfunction "2_P$2") (pintype "bidirectional"))
      (node (ref "C60") (pin "2") (pinfunction "2_2") (pintype "bidirectional"))
      (node (ref "C61") (pin "2") (pinfunction "2_2") (pintype "bidirectional"))
      (node (ref "C62") (pin "P$2") (pinfunction "2_P$2") (pintype "bidirectional"))
      (node (ref "C63") (pin "P$2") (pinfunction "2_P$2") (pintype "bidirectional"))
      (node (ref "C64") (pin "P$2") (pinfunction "2_P$2") (pintype "bidirectional"))
      (node (ref "C7") (pin "P$2") (pinfunction "2_P$2") (pintype "bidirectional"))
      (node (ref "C8") (pin "P$2") (pinfunction "2_P$2") (pintype "bidirectional"))
      (node (ref "C9") (pin "P$2") (pinfunction "2_P$2") (pintype "bidirectional"))
      (node (ref "IC1") (pin "102") (pinfunction "VSS_102") (pintype "power_in"))
      (node (ref "IC1") (pin "113") (pinfunction "VSS_113") (pintype "power_in"))
      (node (ref "IC1") (pin "126") (pinfunction "VSS_126") (pintype "power_in"))
      (node (ref "IC1") (pin "135") (pinfunction "VSS_135") (pintype "power_in"))
      (node (ref "IC1") (pin "14") (pinfunction "VSS_14") (pintype "power_in"))
      (node (ref "IC1") (pin "148") (pinfunction "VSS_148") (pintype "power_in"))
      (node (ref "IC1") (pin "158") (pinfunction "VSS_158") (pintype "power_in"))
      (node (ref "IC1") (pin "22") (pinfunction "VSS_22") (pintype "power_in"))
      (node (ref "IC1") (pin "37") (pinfunction "VSSA_37") (pintype "power_in"))
      (node (ref "IC1") (pin "61") (pinfunction "VSS_61") (pintype "power_in"))
      (node (ref "IC1") (pin "71") (pinfunction "VSS_71") (pintype "power_in"))
      (node (ref "IC1") (pin "90") (pinfunction "VSS_90") (pintype "power_in"))
      (node (ref "IC2") (pin "12") (pinfunction "GNDQ_12") (pintype "power_in"))
      (node (ref "IC2") (pin "28") (pinfunction "GND_28") (pintype "power_in"))
      (node (ref "IC2") (pin "41") (pinfunction "GND_41") (pintype "power_in"))
      (node (ref "IC2") (pin "46") (pinfunction "GNDQ_46") (pintype "power_in"))
      (node (ref "IC2") (pin "52") (pinfunction "GNDQ_52") (pintype "power_in"))
      (node (ref "IC2") (pin "54") (pinfunction "GND_54") (pintype "power_in"))
      (node (ref "IC2") (pin "6") (pinfunction "GNDQ_6") (pintype "power_in"))
      (node (ref "PWR_LED") (pin "C") (pinfunction "C_C") (pintype "passive"))
      (node (ref "R5") (pin "2") (pinfunction "2_2") (pintype "passive"))
      (node (ref "U$2") (pin "2") (pinfunction "2_2") (pintype "bidirectional"))
      (node (ref "U$7") (pin "10") (pinfunction "0P4V_10") (pintype "bidirectional"))
      (node (ref "U$7") (pin "7") (pinfunction "GND_7") (pintype "bidirectional"))
      (node (ref "U$7") (pin "TP") (pinfunction "TP_TP") (pintype "bidirectional"))
      (node (ref "U$8") (pin "11") (pinfunction "0P2V_11") (pintype "bidirectional"))
      (node (ref "U$8") (pin "12") (pinfunction "0P1V_12") (pintype "bidirectional"))
      (node (ref "U$8") (pin "7") (pinfunction "GND_7") (pintype "bidirectional"))
      (node (ref "U$8") (pin "8") (pinfunction "1P6V_8") (pintype "bidirectional"))
      (node (ref "U$8") (pin "TP") (pinfunction "TP_TP") (pintype "bidirectional"))
      (node (ref "U$9") (pin "11") (pinfunction "0P2V_11") (pintype "bidirectional"))
      (node (ref "U$9") (pin "12") (pinfunction "0P1V_12") (pintype "bidirectional"))
      (node (ref "U$9") (pin "7") (pinfunction "GND_7") (pintype "bidirectional"))
      (node (ref "U$9") (pin "8") (pinfunction "1P6V_8") (pintype "bidirectional"))
      (node (ref "U$9") (pin "TP") (pinfunction "TP_TP") (pintype "bidirectional"))
      (node (ref "U1") (pin "16") (pinfunction "DGND_16") (pintype "power_in"))
      (node (ref "U1") (pin "20") (pinfunction "DGND_20") (pintype "power_in"))
      (node (ref "U1") (pin "21") (pinfunction "DGND_21") (pintype "power_in"))
      (node (ref "U1") (pin "22") (pinfunction "DGND_22") (pintype "power_in"))
      (node (ref "U1") (pin "35") (pinfunction "DGND_35") (pintype "power_in"))
      (node (ref "U1") (pin "37") (pinfunction "AGND_37") (pintype "power_in"))
      (node (ref "U1") (pin "4") (pinfunction "DGND_4") (pintype "power_in"))
      (node (ref "U1") (pin "40") (pinfunction "AGND_40") (pintype "power_in"))
      (node (ref "U1") (pin "41") (pinfunction "AGND_41") (pintype "power_in"))
      (node (ref "U1") (pin "47") (pinfunction "AGND_47") (pintype "power_in"))
      (node (ref "X1") (pin "5") (pinfunction "5_5") (pintype "input"))
    )
    (net (code "13") (name "MISO3") (class "Default")
      (node (ref "IC1") (pin "140") (pinfunction "PC11_140") (pintype "bidirectional"))
      (node (ref "U1") (pin "30") (pinfunction "SO_30") (pintype "output"))
    )
    (net (code "14") (name "MOSI3") (class "Default")
      (node (ref "IC1") (pin "141") (pinfunction "PC12_141") (pintype "bidirectional"))
      (node (ref "U1") (pin "29") (pinfunction "SI_29") (pintype "input"))
    )
    (net (code "15") (name "MP3_CS#") (class "Default")
      (node (ref "IC1") (pin "117") (pinfunction "PC8_117") (pintype "bidirectional"))
      (node (ref "U1") (pin "23") (pinfunction "XCS_23") (pintype "input"))
    )
    (net (code "16") (name "MP3_DCS") (class "Default")
      (node (ref "IC1") (pin "118") (pinfunction "PC9_118") (pintype "bidirectional"))
      (node (ref "U1") (pin "13") (pinfunction "XDCS/BSYNC_13") (pintype "input"))
    )
    (net (code "17") (name "MP3_DREQ") (class "Default")
      (node (ref "IC1") (pin "115") (pinfunction "PC6_115") (pintype "bidirectional"))
      (node (ref "U1") (pin "8") (pinfunction "DREQ_8") (pintype "output"))
    )
    (net (code "18") (name "MP3_RST#") (class "Default")
      (node (ref "IC1") (pin "116") (pinfunction "PC7_116") (pintype "bidirectional"))
      (node (ref "U1") (pin "3") (pinfunction "XRESET_3") (pintype "input"))
    )
    (net (code "19") (name "N$11") (class "Default")
      (node (ref "X1") (pin "1") (pinfunction "1_1") (pintype "input"))
    )
    (net (code "20") (name "NRST") (class "Default")
      (node (ref "C26") (pin "2") (pinfunction "2_2") (pintype "passive"))
      (node (ref "IC1") (pin "31") (pinfunction "NRST_31") (pintype "bidirectional"))
      (node (ref "R3") (pin "1") (pinfunction "1_1") (pintype "passive"))
      (node (ref "U$2") (pin "1") (pinfunction "1_1") (pintype "bidirectional"))
    )
    (net (code "21") (name "Net-(C2-Pad2)") (class "Default")
      (node (ref "C2") (pin "2") (pinfunction "2_2") (pintype "passive"))
      (node (ref "Q1_STM") (pin "1") (pinfunction "1_1") (pintype "passive"))
      (node (ref "R1") (pin "1") (pinfunction "1_1") (pintype "passive"))
    )
    (net (code "22") (name "Net-(C3-2)") (class "Default")
      (node (ref "C3") (pin "P$2") (pinfunction "2_P$2") (pintype "bidirectional"))
      (node (ref "U1") (pin "18") (pinfunction "XTALI_18") (pintype "input"))
      (node (ref "Y1") (pin "2") (pinfunction "2_2") (pintype "passive"))
    )
    (net (code "23") (name "Net-(C4-2)") (class "Default")
      (node (ref "C4") (pin "P$2") (pinfunction "2_P$2") (pintype "bidirectional"))
      (node (ref "U1") (pin "17") (pinfunction "XTALO_17") (pintype "output"))
      (node (ref "Y1") (pin "1") (pinfunction "1_1") (pintype "passive"))
    )
    (net (code "24") (name "Net-(C27-Pad1)") (class "Default")
      (node (ref "C27") (pin "1") (pinfunction "1_1") (pintype "passive"))
      (node (ref "R6") (pin "1") (pinfunction "1_1") (pintype "passive"))
    )
    (net (code "25") (name "Net-(C27-Pad2)") (class "Default")
      (node (ref "C27") (pin "2") (pinfunction "2_2") (pintype "passive"))
      (node (ref "R4") (pin "1") (pinfunction "1_1") (pintype "passive"))
      (node (ref "R5") (pin "1") (pinfunction "1_1") (pintype "passive"))
      (node (ref "U$1") (pin "1") (pinfunction "1_1") (pintype "bidirectional"))
    )
    (net (code "26") (name "Net-(PWR_LED-PadA)") (class "Default")
      (node (ref "PWR_LED") (pin "A") (pinfunction "A_A") (pintype "passive"))
      (node (ref "R2_PWR_LED") (pin "2") (pinfunction "2_2") (pintype "passive"))
    )
    (net (code "27") (name "OSC_IN") (class "Default")
      (node (ref "C1") (pin "2") (pinfunction "2_2") (pintype "passive"))
      (node (ref "IC1") (pin "29") (pinfunction "PH0/OSC_IN_29") (pintype "bidirectional"))
      (node (ref "Q1_STM") (pin "3") (pinfunction "2_3") (pintype "passive"))
    )
    (net (code "28") (name "OSC_OUT") (class "Default")
      (node (ref "IC1") (pin "30") (pinfunction "PH1/OSC_OUT_30") (pintype "bidirectional"))
      (node (ref "R1") (pin "2") (pinfunction "2_2") (pintype "passive"))
    )
    (net (code "29") (name "PA0_WKUP") (class "Default")
      (node (ref "IC1") (pin "40") (pinfunction "PA0/WKUP_40") (pintype "bidirectional"))
      (node (ref "R4") (pin "2") (pinfunction "2_2") (pintype "passive"))
    )
    (net (code "30") (name "PA1") (class "Default")
      (node (ref "IC1") (pin "41") (pinfunction "PA1_41") (pintype "bidirectional"))
    )
    (net (code "31") (name "PA2") (class "Default")
      (node (ref "IC1") (pin "42") (pinfunction "PA2_42") (pintype "bidirectional"))
    )
    (net (code "32") (name "PA3") (class "Default")
      (node (ref "IC1") (pin "47") (pinfunction "PA3_47") (pintype "bidirectional"))
    )
    (net (code "33") (name "PA4") (class "Default")
      (node (ref "IC1") (pin "50") (pinfunction "PA4_50") (pintype "bidirectional"))
    )
    (net (code "34") (name "PA5") (class "Default")
      (node (ref "IC1") (pin "51") (pinfunction "PA5_51") (pintype "bidirectional"))
    )
    (net (code "35") (name "PA6") (class "Default")
      (node (ref "IC1") (pin "52") (pinfunction "PA6_52") (pintype "bidirectional"))
    )
    (net (code "36") (name "PA7") (class "Default")
      (node (ref "IC1") (pin "53") (pinfunction "PA7_53") (pintype "bidirectional"))
    )
    (net (code "37") (name "PA8") (class "Default")
      (node (ref "IC1") (pin "119") (pinfunction "PA8_119") (pintype "bidirectional"))
    )
    (net (code "38") (name "PA9") (class "Default")
      (node (ref "IC1") (pin "120") (pinfunction "PA9_120") (pintype "bidirectional"))
    )
    (net (code "39") (name "PA10") (class "Default")
      (node (ref "IC1") (pin "121") (pinfunction "PA10_121") (pintype "bidirectional"))
    )
    (net (code "40") (name "PA11") (class "Default")
      (node (ref "IC1") (pin "122") (pinfunction "PA11_122") (pintype "bidirectional"))
    )
    (net (code "41") (name "PA12") (class "Default")
      (node (ref "IC1") (pin "123") (pinfunction "PA12_123") (pintype "bidirectional"))
    )
    (net (code "42") (name "PA13") (class "Default")
      (node (ref "IC1") (pin "124") (pinfunction "PA13/JTMS-SWDIO_124") (pintype "bidirectional"))
    )
    (net (code "43") (name "PA14") (class "Default")
      (node (ref "IC1") (pin "137") (pinfunction "PA14/JTCK-SWCLK_137") (pintype "bidirectional"))
    )
    (net (code "44") (name "PA15") (class "Default")
      (node (ref "IC1") (pin "138") (pinfunction "PA15/JTDI_138") (pintype "bidirectional"))
    )
    (net (code "45") (name "PB0") (class "Default")
      (node (ref "IC1") (pin "56") (pinfunction "PB0_56") (pintype "bidirectional"))
    )
    (net (code "46") (name "PB1") (class "Default")
      (node (ref "IC1") (pin "57") (pinfunction "PB1_57") (pintype "bidirectional"))
    )
    (net (code "47") (name "PB2") (class "Default")
      (node (ref "IC1") (pin "58") (pinfunction "PB2/BOOT1_58") (pintype "bidirectional"))
    )
    (net (code "48") (name "PB3") (class "Default")
      (node (ref "IC1") (pin "161") (pinfunction "PB3/JTDO/TRACE/SWO_161") (pintype "bidirectional"))
    )
    (net (code "49") (name "PB4") (class "Default")
      (node (ref "IC1") (pin "162") (pinfunction "PB4/NJTRST_162") (pintype "bidirectional"))
    )
    (net (code "50") (name "PB5") (class "Default")
      (node (ref "IC1") (pin "163") (pinfunction "PB5_163") (pintype "bidirectional"))
      (node (ref "IC2") (pin "37") (pinfunction "CKE_37") (pintype "input"))
    )
    (net (code "51") (name "PB6") (class "Default")
      (node (ref "IC1") (pin "164") (pinfunction "PB6_164") (pintype "bidirectional"))
      (node (ref "IC2") (pin "19") (pinfunction "CS-_19") (pintype "input"))
    )
    (net (code "52") (name "PB7") (class "Default")
      (node (ref "IC1") (pin "165") (pinfunction "PB7_165") (pintype "bidirectional"))
    )
    (net (code "53") (name "PB8") (class "Default")
      (node (ref "IC1") (pin "167") (pinfunction "PB8_167") (pintype "bidirectional"))
    )
    (net (code "54") (name "PB9") (class "Default")
      (node (ref "IC1") (pin "168") (pinfunction "PB9_168") (pintype "bidirectional"))
    )
    (net (code "55") (name "PB10") (class "Default")
      (node (ref "IC1") (pin "79") (pinfunction "PB10_79") (pintype "bidirectional"))
    )
    (net (code "56") (name "PB11") (class "Default")
      (node (ref "IC1") (pin "80") (pinfunction "PB11_80") (pintype "bidirectional"))
    )
    (net (code "57") (name "PB12") (class "Default")
      (node (ref "IC1") (pin "92") (pinfunction "PB12_92") (pintype "bidirectional"))
    )
    (net (code "58") (name "PB13") (class "Default")
      (node (ref "IC1") (pin "93") (pinfunction "PB13_93") (pintype "bidirectional"))
    )
    (net (code "59") (name "PB14") (class "Default")
      (node (ref "IC1") (pin "94") (pinfunction "PB14_94") (pintype "bidirectional"))
    )
    (net (code "60") (name "PB15") (class "Default")
      (node (ref "IC1") (pin "95") (pinfunction "PB15_95") (pintype "bidirectional"))
    )
    (net (code "61") (name "PC0") (class "Default")
      (node (ref "IC1") (pin "32") (pinfunction "PC0_32") (pintype "bidirectional"))
      (node (ref "IC2") (pin "16") (pinfunction "WE-_16") (pintype "input"))
    )
    (net (code "62") (name "PC1") (class "Default")
      (node (ref "IC1") (pin "33") (pinfunction "PC1_33") (pintype "bidirectional"))
    )
    (net (code "63") (name "PC2") (class "Default")
      (node (ref "IC1") (pin "34") (pinfunction "PC2_34") (pintype "bidirectional"))
    )
    (net (code "64") (name "PC3") (class "Default")
      (node (ref "IC1") (pin "35") (pinfunction "PC3_35") (pintype "bidirectional"))
    )
    (net (code "65") (name "PC4") (class "Default")
      (node (ref "IC1") (pin "54") (pinfunction "PC4_54") (pintype "bidirectional"))
    )
    (net (code "66") (name "PC5") (class "Default")
      (node (ref "IC1") (pin "55") (pinfunction "PC5_55") (pintype "bidirectional"))
    )
    (net (code "67") (name "PC13") (class "Default")
      (node (ref "IC1") (pin "8") (pinfunction "PC13_8") (pintype "bidirectional"))
    )
    (net (code "68") (name "PC14") (class "Default")
      (node (ref "IC1") (pin "9") (pinfunction "PC14/OSC32_IN_9") (pintype "bidirectional"))
    )
    (net (code "69") (name "PC15") (class "Default")
      (node (ref "IC1") (pin "10") (pinfunction "PC15/OSC32_OUT_10") (pintype "bidirectional"))
    )
    (net (code "70") (name "PD0") (class "Default")
      (node (ref "IC1") (pin "142") (pinfunction "PD0_142") (pintype "bidirectional"))
      (node (ref "IC2") (pin "5") (pinfunction "DQ2_5") (pintype "bidirectional"))
    )
    (net (code "71") (name "PD1") (class "Default")
      (node (ref "IC1") (pin "143") (pinfunction "PD1_143") (pintype "bidirectional"))
      (node (ref "IC2") (pin "7") (pinfunction "DQ3_7") (pintype "bidirectional"))
    )
    (net (code "72") (name "PD2") (class "Default")
      (node (ref "IC1") (pin "144") (pinfunction "PD2_144") (pintype "bidirectional"))
    )
    (net (code "73") (name "PD4") (class "Default")
      (node (ref "IC1") (pin "146") (pinfunction "PD4_146") (pintype "bidirectional"))
    )
    (net (code "74") (name "PD5") (class "Default")
      (node (ref "IC1") (pin "147") (pinfunction "PD5_147") (pintype "bidirectional"))
    )
    (net (code "75") (name "PD6") (class "Default")
      (node (ref "IC1") (pin "150") (pinfunction "PD6_150") (pintype "bidirectional"))
    )
    (net (code "76") (name "PD7") (class "Default")
      (node (ref "IC1") (pin "151") (pinfunction "PD7_151") (pintype "bidirectional"))
    )
    (net (code "77") (name "PD8") (class "Default")
      (node (ref "IC1") (pin "96") (pinfunction "PD8_96") (pintype "bidirectional"))
      (node (ref "IC2") (pin "50") (pinfunction "DQ13_50") (pintype "bidirectional"))
    )
    (net (code "78") (name "PD9") (class "Default")
      (node (ref "IC1") (pin "97") (pinfunction "PD9_97") (pintype "bidirectional"))
      (node (ref "IC2") (pin "51") (pinfunction "DQ14_51") (pintype "bidirectional"))
    )
    (net (code "79") (name "PD10") (class "Default")
      (node (ref "IC1") (pin "98") (pinfunction "PD10_98") (pintype "bidirectional"))
      (node (ref "IC2") (pin "53") (pinfunction "DQ15_53") (pintype "bidirectional"))
    )
    (net (code "80") (name "PD11") (class "Default")
      (node (ref "IC1") (pin "99") (pinfunction "PD11_99") (pintype "bidirectional"))
    )
    (net (code "81") (name "PD12") (class "Default")
      (node (ref "IC1") (pin "100") (pinfunction "PD12_100") (pintype "bidirectional"))
    )
    (net (code "82") (name "PD13") (class "Default")
      (node (ref "IC1") (pin "101") (pinfunction "PD13_101") (pintype "bidirectional"))
    )
    (net (code "83") (name "PD14") (class "Default")
      (node (ref "IC1") (pin "104") (pinfunction "PD14_104") (pintype "bidirectional"))
      (node (ref "IC2") (pin "2") (pinfunction "DQ0_2") (pintype "bidirectional"))
    )
    (net (code "84") (name "PD15") (class "Default")
      (node (ref "IC2") (pin "4") (pinfunction "DQ1_4") (pintype "bidirectional"))
    )
    (net (code "85") (name "PDR_ON") (class "Default")
      (node (ref "IC1") (pin "171") (pinfunction "PDR_ON_171") (pintype "power_in"))
    )
    (net (code "86") (name "PE0") (class "Default")
      (node (ref "IC1") (pin "169") (pinfunction "PE0_169") (pintype "bidirectional"))
      (node (ref "IC2") (pin "15") (pinfunction "LDQM_15") (pintype "bidirectional"))
    )
    (net (code "87") (name "PE1") (class "Default")
      (node (ref "IC1") (pin "170") (pinfunction "PE1_170") (pintype "bidirectional"))
      (node (ref "IC2") (pin "39") (pinfunction "UDQM_39") (pintype "bidirectional"))
    )
    (net (code "88") (name "PE2") (class "Default")
      (node (ref "IC1") (pin "1") (pinfunction "PE2_1") (pintype "bidirectional"))
    )
    (net (code "89") (name "PE3") (class "Default")
      (node (ref "IC1") (pin "2") (pinfunction "PE3_2") (pintype "bidirectional"))
    )
    (net (code "90") (name "PE4") (class "Default")
      (node (ref "IC1") (pin "3") (pinfunction "PE4_3") (pintype "bidirectional"))
    )
    (net (code "91") (name "PE5") (class "Default")
      (node (ref "IC1") (pin "4") (pinfunction "PE5_4") (pintype "bidirectional"))
    )
    (net (code "92") (name "PE6") (class "Default")
      (node (ref "IC1") (pin "5") (pinfunction "PE6_5") (pintype "bidirectional"))
    )
    (net (code "93") (name "PE7") (class "Default")
      (node (ref "IC1") (pin "68") (pinfunction "PE7_68") (pintype "bidirectional"))
      (node (ref "IC2") (pin "8") (pinfunction "DQ4_8") (pintype "bidirectional"))
    )
    (net (code "94") (name "PE8") (class "Default")
      (node (ref "IC1") (pin "69") (pinfunction "PE8_69") (pintype "bidirectional"))
      (node (ref "IC2") (pin "10") (pinfunction "DQ5_10") (pintype "bidirectional"))
    )
    (net (code "95") (name "PE9") (class "Default")
      (node (ref "IC1") (pin "70") (pinfunction "PE9_70") (pintype "bidirectional"))
      (node (ref "IC2") (pin "11") (pinfunction "DQ6_11") (pintype "bidirectional"))
    )
    (net (code "96") (name "PE10") (class "Default")
      (node (ref "IC1") (pin "73") (pinfunction "PE10_73") (pintype "bidirectional"))
      (node (ref "IC2") (pin "13") (pinfunction "DQ7_13") (pintype "bidirectional"))
    )
    (net (code "97") (name "PE11") (class "Default")
      (node (ref "IC1") (pin "74") (pinfunction "PE11_74") (pintype "bidirectional"))
      (node (ref "IC2") (pin "42") (pinfunction "DQ8_42") (pintype "bidirectional"))
    )
    (net (code "98") (name "PE12") (class "Default")
      (node (ref "IC1") (pin "75") (pinfunction "PE12_75") (pintype "bidirectional"))
      (node (ref "IC2") (pin "44") (pinfunction "DQ9_44") (pintype "bidirectional"))
    )
    (net (code "99") (name "PE13") (class "Default")
      (node (ref "IC1") (pin "76") (pinfunction "PE13_76") (pintype "bidirectional"))
      (node (ref "IC2") (pin "45") (pinfunction "DQ10_45") (pintype "bidirectional"))
    )
    (net (code "100") (name "PE14") (class "Default")
      (node (ref "IC1") (pin "77") (pinfunction "PE14_77") (pintype "bidirectional"))
      (node (ref "IC2") (pin "47") (pinfunction "DQ11_47") (pintype "bidirectional"))
    )
    (net (code "101") (name "PE15") (class "Default")
      (node (ref "IC1") (pin "78") (pinfunction "PE15_78") (pintype "bidirectional"))
      (node (ref "IC2") (pin "48") (pinfunction "DQ12_48") (pintype "bidirectional"))
    )
    (net (code "102") (name "PF0") (class "Default")
      (node (ref "IC1") (pin "16") (pinfunction "PF0_16") (pintype "bidirectional"))
      (node (ref "IC2") (pin "23") (pinfunction "A0_23") (pintype "input"))
    )
    (net (code "103") (name "PF1") (class "Default")
      (node (ref "IC1") (pin "17") (pinfunction "PF1_17") (pintype "bidirectional"))
      (node (ref "IC2") (pin "24") (pinfunction "A1_24") (pintype "input"))
    )
    (net (code "104") (name "PF2") (class "Default")
      (node (ref "IC1") (pin "18") (pinfunction "PF2_18") (pintype "bidirectional"))
      (node (ref "IC2") (pin "25") (pinfunction "A2_25") (pintype "input"))
    )
    (net (code "105") (name "PF3") (class "Default")
      (node (ref "IC1") (pin "19") (pinfunction "PF3_19") (pintype "bidirectional"))
      (node (ref "IC2") (pin "26") (pinfunction "A3_26") (pintype "input"))
    )
    (net (code "106") (name "PF4") (class "Default")
      (node (ref "IC1") (pin "20") (pinfunction "PF4_20") (pintype "bidirectional"))
      (node (ref "IC2") (pin "29") (pinfunction "A4_29") (pintype "input"))
    )
    (net (code "107") (name "PF5") (class "Default")
      (node (ref "IC1") (pin "21") (pinfunction "PF5_21") (pintype "bidirectional"))
      (node (ref "IC2") (pin "30") (pinfunction "A5_30") (pintype "input"))
    )
    (net (code "108") (name "PF6") (class "Default")
      (node (ref "IC1") (pin "24") (pinfunction "PF6_24") (pintype "bidirectional"))
    )
    (net (code "109") (name "PF7") (class "Default")
      (node (ref "IC1") (pin "25") (pinfunction "PF7_25") (pintype "bidirectional"))
    )
    (net (code "110") (name "PF8") (class "Default")
      (node (ref "IC1") (pin "26") (pinfunction "PF8_26") (pintype "bidirectional"))
    )
    (net (code "111") (name "PF9") (class "Default")
      (node (ref "IC1") (pin "27") (pinfunction "PF9_27") (pintype "bidirectional"))
    )
    (net (code "112") (name "PF10") (class "Default")
      (node (ref "IC1") (pin "28") (pinfunction "PF10_28") (pintype "bidirectional"))
    )
    (net (code "113") (name "PF11") (class "Default")
      (node (ref "IC1") (pin "59") (pinfunction "PF11_59") (pintype "bidirectional"))
      (node (ref "IC2") (pin "18") (pinfunction "RAS-_18") (pintype "input"))
    )
    (net (code "114") (name "PF12") (class "Default")
      (node (ref "IC1") (pin "60") (pinfunction "PF12_60") (pintype "bidirectional"))
      (node (ref "IC2") (pin "31") (pinfunction "A6_31") (pintype "input"))
    )
    (net (code "115") (name "PF13") (class "Default")
      (node (ref "IC1") (pin "63") (pinfunction "PF13_63") (pintype "bidirectional"))
      (node (ref "IC2") (pin "32") (pinfunction "A7_32") (pintype "input"))
    )
    (net (code "116") (name "PF14") (class "Default")
      (node (ref "IC1") (pin "64") (pinfunction "PF14_64") (pintype "bidirectional"))
      (node (ref "IC2") (pin "33") (pinfunction "A8_33") (pintype "input"))
    )
    (net (code "117") (name "PF15") (class "Default")
      (node (ref "IC1") (pin "65") (pinfunction "PF15_65") (pintype "bidirectional"))
      (node (ref "IC2") (pin "34") (pinfunction "A9_34") (pintype "input"))
    )
    (net (code "118") (name "PG0") (class "Default")
      (node (ref "IC1") (pin "66") (pinfunction "PG0_66") (pintype "bidirectional"))
      (node (ref "IC2") (pin "22") (pinfunction "A10_22") (pintype "input"))
    )
    (net (code "119") (name "PG1") (class "Default")
      (node (ref "IC1") (pin "67") (pinfunction "PG1_67") (pintype "bidirectional"))
      (node (ref "IC2") (pin "35") (pinfunction "A11_35") (pintype "input"))
    )
    (net (code "120") (name "PG2") (class "Default")
      (node (ref "IC1") (pin "106") (pinfunction "PG2_106") (pintype "bidirectional"))
    )
    (net (code "121") (name "PG3") (class "Default")
      (node (ref "IC1") (pin "107") (pinfunction "PG3_107") (pintype "bidirectional"))
    )
    (net (code "122") (name "PG4") (class "Default")
      (node (ref "IC1") (pin "108") (pinfunction "PG4_108") (pintype "bidirectional"))
      (node (ref "IC2") (pin "20") (pinfunction "BA0_20") (pintype "bidirectional"))
    )
    (net (code "123") (name "PG5") (class "Default")
      (node (ref "IC1") (pin "109") (pinfunction "PG5_109") (pintype "bidirectional"))
      (node (ref "IC2") (pin "21") (pinfunction "BA1_21") (pintype "bidirectional"))
    )
    (net (code "124") (name "PG6") (class "Default")
      (node (ref "IC1") (pin "110") (pinfunction "PG6_110") (pintype "bidirectional"))
    )
    (net (code "125") (name "PG7") (class "Default")
      (node (ref "IC1") (pin "111") (pinfunction "PG7_111") (pintype "bidirectional"))
    )
    (net (code "126") (name "PG8") (class "Default")
      (node (ref "IC1") (pin "112") (pinfunction "PG8_112") (pintype "bidirectional"))
      (node (ref "IC2") (pin "38") (pinfunction "CLK_38") (pintype "input"))
    )
    (net (code "127") (name "PG9") (class "Default")
      (node (ref "IC1") (pin "152") (pinfunction "PG9_152") (pintype "bidirectional"))
    )
    (net (code "128") (name "PG10") (class "Default")
      (node (ref "IC1") (pin "153") (pinfunction "PG10_153") (pintype "bidirectional"))
    )
    (net (code "129") (name "PG11") (class "Default")
      (node (ref "IC1") (pin "154") (pinfunction "PG11_154") (pintype "bidirectional"))
    )
    (net (code "130") (name "PG12") (class "Default")
      (node (ref "IC1") (pin "155") (pinfunction "PG12_155") (pintype "bidirectional"))
    )
    (net (code "131") (name "PG13") (class "Default")
      (node (ref "IC1") (pin "156") (pinfunction "PG13_156") (pintype "bidirectional"))
    )
    (net (code "132") (name "PG14") (class "Default")
      (node (ref "IC1") (pin "157") (pinfunction "PG14_157") (pintype "bidirectional"))
    )
    (net (code "133") (name "PG15") (class "Default")
      (node (ref "IC1") (pin "160") (pinfunction "PG15_160") (pintype "bidirectional"))
      (node (ref "IC2") (pin "17") (pinfunction "CAS-_17") (pintype "input"))
    )
    (net (code "134") (name "PH2") (class "Default")
      (node (ref "IC1") (pin "43") (pinfunction "PH2_43") (pintype "bidirectional"))
    )
    (net (code "135") (name "PH3") (class "Default")
      (node (ref "IC1") (pin "44") (pinfunction "PH3_44") (pintype "bidirectional"))
    )
    (net (code "136") (name "PH4") (class "Default")
      (node (ref "IC1") (pin "45") (pinfunction "PH4_45") (pintype "bidirectional"))
    )
    (net (code "137") (name "PH5") (class "Default")
      (node (ref "IC1") (pin "46") (pinfunction "PH5_46") (pintype "bidirectional"))
    )
    (net (code "138") (name "PH6") (class "Default")
      (node (ref "IC1") (pin "83") (pinfunction "PH6_83") (pintype "bidirectional"))
    )
    (net (code "139") (name "PH7") (class "Default")
      (node (ref "IC1") (pin "84") (pinfunction "PH7_84") (pintype "bidirectional"))
    )
    (net (code "140") (name "PH8") (class "Default")
      (node (ref "IC1") (pin "85") (pinfunction "PH8_85") (pintype "bidirectional"))
    )
    (net (code "141") (name "PH9") (class "Default")
      (node (ref "IC1") (pin "86") (pinfunction "PH9_86") (pintype "bidirectional"))
    )
    (net (code "142") (name "PH10") (class "Default")
      (node (ref "IC1") (pin "87") (pinfunction "PH10_87") (pintype "bidirectional"))
    )
    (net (code "143") (name "PH11") (class "Default")
      (node (ref "IC1") (pin "88") (pinfunction "PH11_88") (pintype "bidirectional"))
    )
    (net (code "144") (name "PH12") (class "Default")
      (node (ref "IC1") (pin "89") (pinfunction "PH12_89") (pintype "bidirectional"))
    )
    (net (code "145") (name "PH13") (class "Default")
      (node (ref "IC1") (pin "128") (pinfunction "PH13_128") (pintype "bidirectional"))
    )
    (net (code "146") (name "PH14") (class "Default")
      (node (ref "IC1") (pin "129") (pinfunction "PH14_129") (pintype "bidirectional"))
    )
    (net (code "147") (name "PH15") (class "Default")
      (node (ref "IC1") (pin "130") (pinfunction "PH15_130") (pintype "bidirectional"))
    )
    (net (code "148") (name "PI0") (class "Default")
      (node (ref "IC1") (pin "131") (pinfunction "PI0_131") (pintype "bidirectional"))
    )
    (net (code "149") (name "PI1") (class "Default")
      (node (ref "IC1") (pin "132") (pinfunction "PI1_132") (pintype "bidirectional"))
    )
    (net (code "150") (name "PI2") (class "Default")
      (node (ref "IC1") (pin "133") (pinfunction "PI2_133") (pintype "bidirectional"))
    )
    (net (code "151") (name "PI3") (class "Default")
      (node (ref "IC1") (pin "134") (pinfunction "PI3_134") (pintype "bidirectional"))
    )
    (net (code "152") (name "PI4") (class "Default")
      (node (ref "IC1") (pin "173") (pinfunction "PI4_173") (pintype "bidirectional"))
    )
    (net (code "153") (name "PI5") (class "Default")
      (node (ref "IC1") (pin "174") (pinfunction "PI5_174") (pintype "bidirectional"))
    )
    (net (code "154") (name "PI6") (class "Default")
      (node (ref "IC1") (pin "175") (pinfunction "PI6_175") (pintype "bidirectional"))
    )
    (net (code "155") (name "PI7") (class "Default")
      (node (ref "IC1") (pin "176") (pinfunction "PI7_176") (pintype "bidirectional"))
    )
    (net (code "156") (name "PI8") (class "Default")
      (node (ref "IC1") (pin "7") (pinfunction "PI8_7") (pintype "bidirectional"))
    )
    (net (code "157") (name "PI9") (class "Default")
      (node (ref "IC1") (pin "11") (pinfunction "PI9_11") (pintype "bidirectional"))
    )
    (net (code "158") (name "PI10") (class "Default")
      (node (ref "IC1") (pin "12") (pinfunction "PI10_12") (pintype "bidirectional"))
    )
    (net (code "159") (name "PI11") (class "Default")
      (node (ref "IC1") (pin "13") (pinfunction "PI11_13") (pintype "bidirectional"))
    )
    (net (code "160") (name "SCK3") (class "Default")
      (node (ref "IC1") (pin "139") (pinfunction "PC10_139") (pintype "bidirectional"))
      (node (ref "U1") (pin "28") (pinfunction "SCLK_28") (pintype "input"))
    )
    (net (code "161") (name "SD_CD#") (class "Default")
      (node (ref "IC1") (pin "105") (pinfunction "PD15_105") (pintype "bidirectional"))
    )
    (net (code "162") (name "SD_CS#") (class "Default")
      (node (ref "IC1") (pin "145") (pinfunction "PD3_145") (pintype "bidirectional"))
    )
    (net (code "163") (name "VCAP_1") (class "Default")
      (node (ref "IC1") (pin "81") (pinfunction "VCAP_1_81") (pintype "power_in"))
    )
    (net (code "164") (name "VCAP_2") (class "Default")
      (node (ref "IC1") (pin "125") (pinfunction "VCAP_2_125") (pintype "power_in"))
    )
    (net (code "165") (name "VREF+") (class "Default")
      (node (ref "IC1") (pin "38") (pinfunction "VREF+_38") (pintype "power_in"))
    )
    (net (code "166") (name "unconnected-(IC1-BOOT0-Pad166)") (class "Default")
      (node (ref "IC1") (pin "166") (pinfunction "BOOT0_166") (pintype "input"))
    )
    (net (code "167") (name "unconnected-(IC1-BYPASS_REG-Pad48)") (class "Default")
      (node (ref "IC1") (pin "48") (pinfunction "BYPASS_REG_48") (pintype "input"))
    )
    (net (code "168") (name "unconnected-(IC2-NC-Pad36)") (class "Default")
      (node (ref "IC2") (pin "36") (pinfunction "NC_36") (pintype "no_connect"))
    )
    (net (code "169") (name "unconnected-(IC2-NC-Pad40)") (class "Default")
      (node (ref "IC2") (pin "40") (pinfunction "NC_40") (pintype "no_connect"))
    )
    (net (code "170") (name "unconnected-(U$7-0P1V-Pad12)") (class "Default")
      (node (ref "U$7") (pin "12") (pinfunction "0P1V_12") (pintype "bidirectional"))
    )
    (net (code "171") (name "unconnected-(U$7-0P2V-Pad11)") (class "Default")
      (node (ref "U$7") (pin "11") (pinfunction "0P2V_11") (pintype "bidirectional"))
    )
    (net (code "172") (name "unconnected-(U$7-0P8V-Pad9)") (class "Default")
      (node (ref "U$7") (pin "9") (pinfunction "0P8V_9") (pintype "bidirectional"))
    )
    (net (code "173") (name "unconnected-(U$7-1P6V-Pad8)") (class "Default")
      (node (ref "U$7") (pin "8") (pinfunction "1P6V_8") (pintype "bidirectional"))
    )
    (net (code "174") (name "unconnected-(U$7-3P2V-Pad6)") (class "Default")
      (node (ref "U$7") (pin "6") (pinfunction "3P2V_6") (pintype "bidirectional"))
    )
    (net (code "175") (name "unconnected-(U$7-6P4V1-Pad5)") (class "Default")
      (node (ref "U$7") (pin "5") (pinfunction "6P4V1_5") (pintype "bidirectional"))
    )
    (net (code "176") (name "unconnected-(U$7-6P4V2-Pad4)") (class "Default")
      (node (ref "U$7") (pin "4") (pinfunction "6P4V2_4") (pintype "bidirectional"))
    )
    (net (code "177") (name "unconnected-(U$7-NC-Pad2)") (class "Default")
      (node (ref "U$7") (pin "2") (pinfunction "NC_2") (pintype "bidirectional"))
    )
    (net (code "178") (name "unconnected-(U$7-NC-Pad17)") (class "Default")
      (node (ref "U$7") (pin "17") (pinfunction "NC_17") (pintype "bidirectional"))
    )
    (net (code "179") (name "unconnected-(U$7-NC-Pad18)") (class "Default")
      (node (ref "U$7") (pin "18") (pinfunction "NC_18") (pintype "bidirectional"))
    )
    (net (code "180") (name "unconnected-(U$7-NC-Pad19)") (class "Default")
      (node (ref "U$7") (pin "19") (pinfunction "NC_19") (pintype "bidirectional"))
    )
    (net (code "181") (name "unconnected-(U$8-0P4V-Pad10)") (class "Default")
      (node (ref "U$8") (pin "10") (pinfunction "0P4V_10") (pintype "bidirectional"))
    )
    (net (code "182") (name "unconnected-(U$8-0P8V-Pad9)") (class "Default")
      (node (ref "U$8") (pin "9") (pinfunction "0P8V_9") (pintype "bidirectional"))
    )
    (net (code "183") (name "unconnected-(U$8-3P2V-Pad6)") (class "Default")
      (node (ref "U$8") (pin "6") (pinfunction "3P2V_6") (pintype "bidirectional"))
    )
    (net (code "184") (name "unconnected-(U$8-6P4V1-Pad5)") (class "Default")
      (node (ref "U$8") (pin "5") (pinfunction "6P4V1_5") (pintype "bidirectional"))
    )
    (net (code "185") (name "unconnected-(U$8-6P4V2-Pad4)") (class "Default")
      (node (ref "U$8") (pin "4") (pinfunction "6P4V2_4") (pintype "bidirectional"))
    )
    (net (code "186") (name "unconnected-(U$8-NC-Pad2)") (class "Default")
      (node (ref "U$8") (pin "2") (pinfunction "NC_2") (pintype "bidirectional"))
    )
    (net (code "187") (name "unconnected-(U$8-NC-Pad17)") (class "Default")
      (node (ref "U$8") (pin "17") (pinfunction "NC_17") (pintype "bidirectional"))
    )
    (net (code "188") (name "unconnected-(U$8-NC-Pad18)") (class "Default")
      (node (ref "U$8") (pin "18") (pinfunction "NC_18") (pintype "bidirectional"))
    )
    (net (code "189") (name "unconnected-(U$8-NC-Pad19)") (class "Default")
      (node (ref "U$8") (pin "19") (pinfunction "NC_19") (pintype "bidirectional"))
    )
    (net (code "190") (name "unconnected-(U$9-0P4V-Pad10)") (class "Default")
      (node (ref "U$9") (pin "10") (pinfunction "0P4V_10") (pintype "bidirectional"))
    )
    (net (code "191") (name "unconnected-(U$9-0P8V-Pad9)") (class "Default")
      (node (ref "U$9") (pin "9") (pinfunction "0P8V_9") (pintype "bidirectional"))
    )
    (net (code "192") (name "unconnected-(U$9-3P2V-Pad6)") (class "Default")
      (node (ref "U$9") (pin "6") (pinfunction "3P2V_6") (pintype "bidirectional"))
    )
    (net (code "193") (name "unconnected-(U$9-6P4V1-Pad5)") (class "Default")
      (node (ref "U$9") (pin "5") (pinfunction "6P4V1_5") (pintype "bidirectional"))
    )
    (net (code "194") (name "unconnected-(U$9-6P4V2-Pad4)") (class "Default")
      (node (ref "U$9") (pin "4") (pinfunction "6P4V2_4") (pintype "bidirectional"))
    )
    (net (code "195") (name "unconnected-(U$9-NC-Pad2)") (class "Default")
      (node (ref "U$9") (pin "2") (pinfunction "NC_2") (pintype "bidirectional"))
    )
    (net (code "196") (name "unconnected-(U$9-NC-Pad17)") (class "Default")
      (node (ref "U$9") (pin "17") (pinfunction "NC_17") (pintype "bidirectional"))
    )
    (net (code "197") (name "unconnected-(U$9-NC-Pad18)") (class "Default")
      (node (ref "U$9") (pin "18") (pinfunction "NC_18") (pintype "bidirectional"))
    )
    (net (code "198") (name "unconnected-(U$9-NC-Pad19)") (class "Default")
      (node (ref "U$9") (pin "19") (pinfunction "NC_19") (pintype "bidirectional"))
    )
    (net (code "199") (name "unconnected-(U1A-GBUF-Pad42)") (class "Default")
      (node (ref "U1") (pin "42") (pinfunction "GBUF_42") (pintype "output"))
    )
    (net (code "200") (name "unconnected-(U1A-GPIO0-Pad33)") (class "Default")
      (node (ref "U1") (pin "33") (pinfunction "GPIO0_33") (pintype "bidirectional"))
    )
    (net (code "201") (name "unconnected-(U1A-GPIO1-Pad34)") (class "Default")
      (node (ref "U1") (pin "34") (pinfunction "GPIO1_34") (pintype "bidirectional"))
    )
    (net (code "202") (name "unconnected-(U1A-GPIO2{slash}DCLK-Pad9)") (class "Default")
      (node (ref "U1") (pin "9") (pinfunction "GPIO2/DCLK_9") (pintype "bidirectional"))
    )
    (net (code "203") (name "unconnected-(U1A-GPIO3{slash}SDATA-Pad10)") (class "Default")
      (node (ref "U1") (pin "10") (pinfunction "GPIO3/SDATA_10") (pintype "bidirectional"))
    )
    (net (code "204") (name "unconnected-(U1A-GPIO4{slash}I2S_LROUT-Pad36)") (class "Default")
      (node (ref "U1") (pin "36") (pinfunction "GPIO4/I2S_LROUT_36") (pintype "bidirectional"))
    )
    (net (code "205") (name "unconnected-(U1A-GPIO5{slash}I2S_MCLK-Pad25)") (class "Default")
      (node (ref "U1") (pin "25") (pinfunction "GPIO5/I2S_MCLK_25") (pintype "bidirectional"))
    )
    (net (code "206") (name "unconnected-(U1A-GPIO6{slash}I2S_SCLK-Pad11)") (class "Default")
      (node (ref "U1") (pin "11") (pinfunction "GPIO6/I2S_SCLK_11") (pintype "bidirectional"))
    )
    (net (code "207") (name "unconnected-(U1A-GPIO7{slash}I2S_DATA-Pad12)") (class "Default")
      (node (ref "U1") (pin "12") (pinfunction "GPIO7/I2S_DATA_12") (pintype "bidirectional"))
    )
    (net (code "208") (name "unconnected-(U1A-LEFT-Pad46)") (class "Default")
      (node (ref "U1") (pin "46") (pinfunction "LEFT_46") (pintype "output"))
    )
    (net (code "209") (name "unconnected-(U1A-LINEINR-Pad48)") (class "Default")
      (node (ref "U1") (pin "48") (pinfunction "LINEINR_48") (pintype "input"))
    )
    (net (code "210") (name "unconnected-(U1A-MICN-Pad2)") (class "Default")
      (node (ref "U1") (pin "2") (pinfunction "MICN_2") (pintype "input"))
    )
    (net (code "211") (name "unconnected-(U1A-MICP{slash}LINEINL-Pad1)") (class "Default")
      (node (ref "U1") (pin "1") (pinfunction "MICP/LINEINL_1") (pintype "input"))
    )
    (net (code "212") (name "unconnected-(U1A-RCAP-Pad44)") (class "Default")
      (node (ref "U1") (pin "44") (pinfunction "RCAP_44") (pintype "bidirectional"))
    )
    (net (code "213") (name "unconnected-(U1A-RIGHT-Pad39)") (class "Default")
      (node (ref "U1") (pin "39") (pinfunction "RIGHT_39") (pintype "output"))
    )
    (net (code "214") (name "unconnected-(U1A-RX-Pad26)") (class "Default")
      (node (ref "U1") (pin "26") (pinfunction "RX_26") (pintype "input"))
    )
    (net (code "215") (name "unconnected-(U1A-TEST-Pad32)") (class "Default")
      (node (ref "U1") (pin "32") (pinfunction "TEST_32") (pintype "input"))
    )
    (net (code "216") (name "unconnected-(U1A-TX-Pad27)") (class "Default")
      (node (ref "U1") (pin "27") (pinfunction "TX_27") (pintype "output"))
    )
    (net (code "217") (name "unconnected-(U1A-VCO-Pad15)") (class "Default")
      (node (ref "U1") (pin "15") (pinfunction "VCO_15") (pintype "output"))
    )
    (net (code "218") (name "unconnected-(X1-Pad2)") (class "Default")
      (node (ref "X1") (pin "2") (pinfunction "2_2") (pintype "input"))
    )
    (net (code "219") (name "unconnected-(X1-Pad3)") (class "Default")
      (node (ref "X1") (pin "3") (pinfunction "3_3") (pintype "input"))
    )
    (net (code "220") (name "unconnected-(X1-Pad4)") (class "Default")
      (node (ref "X1") (pin "4") (pinfunction "4_4") (pintype "input"))
    )
  )
)
